# ANET3D_Board.net
KiCad netlist of a schematic drawn in EAGLE
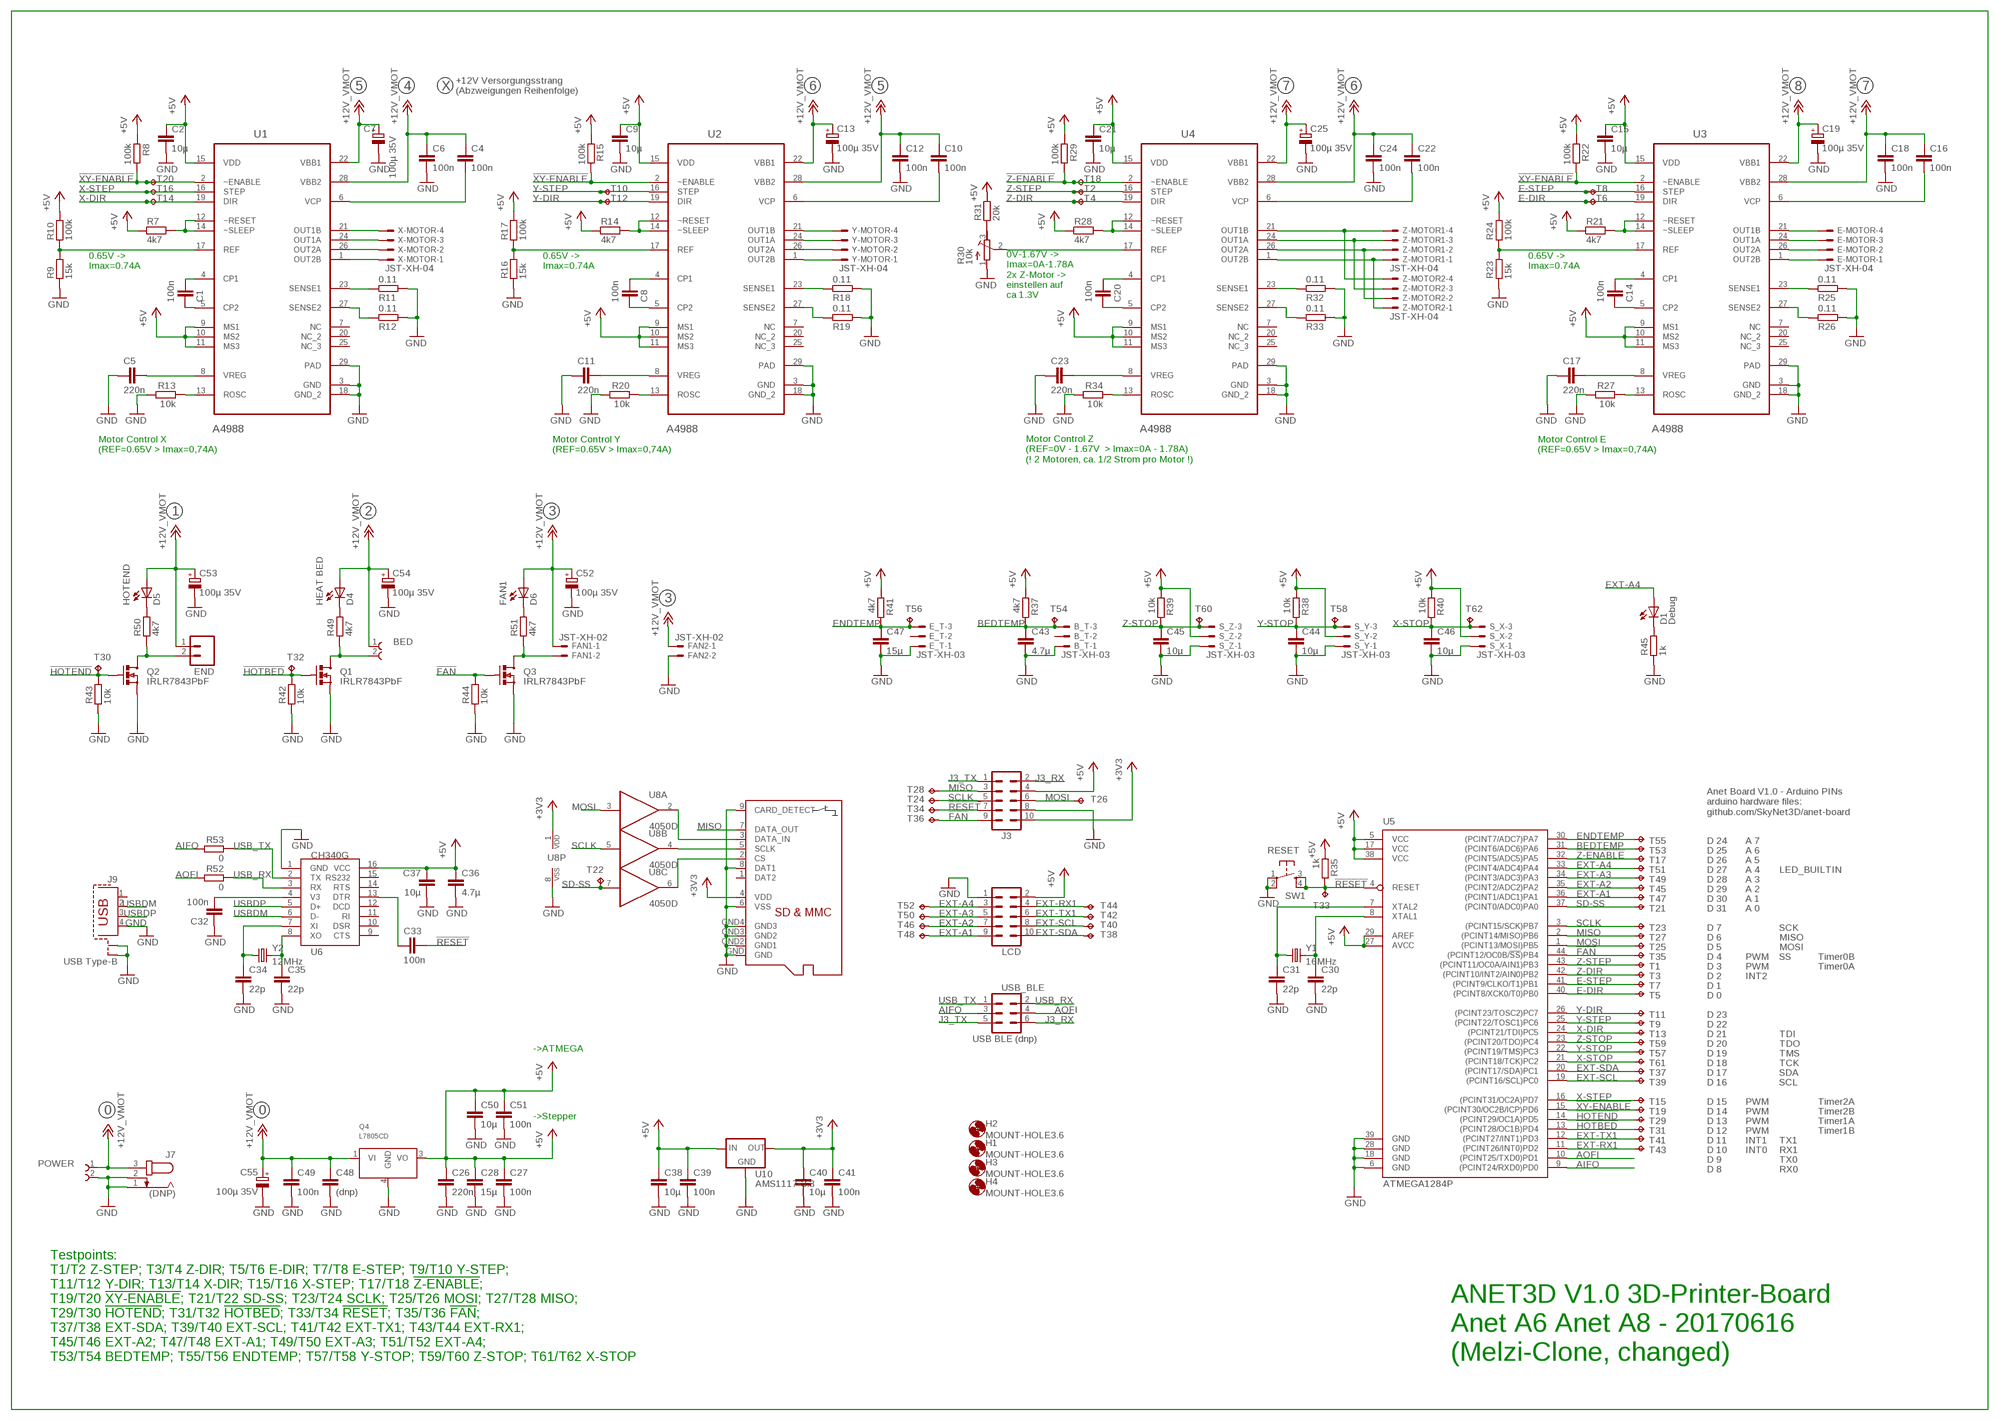
[diagram p0: schematic, sheet 1]

(export (version "E")
  (design (tool "Eeschema 10.0.6"))
  (components
    (comp (ref "BED")
      (value "691311400002")
      (footprint "eagle-import:691311400002")
      (libsource (lib "eagle-import") (part "691311400002"))
    )
    (comp (ref "B_T")
      (value "JST-XH-03")
      (footprint "eagle-import:JST-XH-03-PACKAGE-ROUND-PAD")
      (libsource (lib "eagle-import") (part "JST-XH-03-PIN-ROUND-PAD"))
    )
    (comp (ref "C1")
      (value "100n")
      (footprint "eagle-import:C0805")
      (libsource (lib "eagle-import") (part "C-EUC0805"))
    )
    (comp (ref "C2")
      (value "10µ")
      (footprint "eagle-import:C0805")
      (libsource (lib "eagle-import") (part "C-EUC0805"))
    )
    (comp (ref "C4")
      (value "100n")
      (footprint "eagle-import:C0805")
      (libsource (lib "eagle-import") (part "C-EUC0805"))
    )
    (comp (ref "C5")
      (value "220n")
      (footprint "eagle-import:C0805")
      (libsource (lib "eagle-import") (part "C-EUC0805"))
    )
    (comp (ref "C6")
      (value "100n")
      (footprint "eagle-import:C0805")
      (libsource (lib "eagle-import") (part "C-EUC0805"))
    )
    (comp (ref "C7")
      (value "100µ 35V")
      (footprint "eagle-import:PANASONIC_D")
      (libsource (lib "eagle-import") (part "CPOL-EUD"))
    )
    (comp (ref "C8")
      (value "100n")
      (footprint "eagle-import:C0805")
      (libsource (lib "eagle-import") (part "C-EUC0805"))
    )
    (comp (ref "C9")
      (value "10µ")
      (footprint "eagle-import:C0805")
      (libsource (lib "eagle-import") (part "C-EUC0805"))
    )
    (comp (ref "C10")
      (value "100n")
      (footprint "eagle-import:C0805")
      (libsource (lib "eagle-import") (part "C-EUC0805"))
    )
    (comp (ref "C11")
      (value "220n")
      (footprint "eagle-import:C0805")
      (libsource (lib "eagle-import") (part "C-EUC0805"))
    )
    (comp (ref "C12")
      (value "100n")
      (footprint "eagle-import:C0805")
      (libsource (lib "eagle-import") (part "C-EUC0805"))
    )
    (comp (ref "C13")
      (value "100µ 35V")
      (footprint "eagle-import:PANASONIC_D")
      (libsource (lib "eagle-import") (part "CPOL-EUD"))
    )
    (comp (ref "C14")
      (value "100n")
      (footprint "eagle-import:C0805")
      (libsource (lib "eagle-import") (part "C-EUC0805"))
    )
    (comp (ref "C15")
      (value "10µ")
      (footprint "eagle-import:C0805")
      (libsource (lib "eagle-import") (part "C-EUC0805"))
    )
    (comp (ref "C16")
      (value "100n")
      (footprint "eagle-import:C0805")
      (libsource (lib "eagle-import") (part "C-EUC0805"))
    )
    (comp (ref "C17")
      (value "220n")
      (footprint "eagle-import:C0805")
      (libsource (lib "eagle-import") (part "C-EUC0805"))
    )
    (comp (ref "C18")
      (value "100n")
      (footprint "eagle-import:C0805")
      (libsource (lib "eagle-import") (part "C-EUC0805"))
    )
    (comp (ref "C19")
      (value "100µ 35V")
      (footprint "eagle-import:PANASONIC_D")
      (libsource (lib "eagle-import") (part "CPOL-EUD"))
    )
    (comp (ref "C20")
      (value "100n")
      (footprint "eagle-import:C0805")
      (libsource (lib "eagle-import") (part "C-EUC0805"))
    )
    (comp (ref "C21")
      (value "10µ")
      (footprint "eagle-import:C0805")
      (libsource (lib "eagle-import") (part "C-EUC0805"))
    )
    (comp (ref "C22")
      (value "100n")
      (footprint "eagle-import:C0805")
      (libsource (lib "eagle-import") (part "C-EUC0805"))
    )
    (comp (ref "C23")
      (value "220n")
      (footprint "eagle-import:C0805")
      (libsource (lib "eagle-import") (part "C-EUC0805"))
    )
    (comp (ref "C24")
      (value "100n")
      (footprint "eagle-import:C0805")
      (libsource (lib "eagle-import") (part "C-EUC0805"))
    )
    (comp (ref "C25")
      (value "100µ 35V")
      (footprint "eagle-import:PANASONIC_D")
      (libsource (lib "eagle-import") (part "CPOL-EUD"))
    )
    (comp (ref "C26")
      (value "220n")
      (footprint "eagle-import:C0805")
      (libsource (lib "eagle-import") (part "C-EUC0805"))
    )
    (comp (ref "C27")
      (value "100n")
      (footprint "eagle-import:C0805")
      (libsource (lib "eagle-import") (part "C-EUC0805"))
    )
    (comp (ref "C28")
      (value "15µ")
      (footprint "eagle-import:C0805")
      (libsource (lib "eagle-import") (part "C-EUC0805"))
    )
    (comp (ref "C30")
      (value "22p")
      (footprint "eagle-import:C0805")
      (libsource (lib "eagle-import") (part "C-EUC0805"))
    )
    (comp (ref "C31")
      (value "22p")
      (footprint "eagle-import:C0805")
      (libsource (lib "eagle-import") (part "C-EUC0805"))
    )
    (comp (ref "C32")
      (value "100n")
      (footprint "eagle-import:C0805")
      (libsource (lib "eagle-import") (part "C-EUC0805"))
    )
    (comp (ref "C33")
      (value "100n")
      (footprint "eagle-import:C0805")
      (libsource (lib "eagle-import") (part "C-EUC0805"))
    )
    (comp (ref "C34")
      (value "22p")
      (footprint "eagle-import:C0805")
      (libsource (lib "eagle-import") (part "C-EUC0805"))
    )
    (comp (ref "C35")
      (value "22p")
      (footprint "eagle-import:C0805")
      (libsource (lib "eagle-import") (part "C-EUC0805"))
    )
    (comp (ref "C36")
      (value "4.7µ")
      (footprint "eagle-import:C0805")
      (libsource (lib "eagle-import") (part "C-EUC0805"))
    )
    (comp (ref "C37")
      (value "10µ")
      (footprint "eagle-import:C0805")
      (libsource (lib "eagle-import") (part "C-EUC0805"))
    )
    (comp (ref "C38")
      (value "10µ")
      (footprint "eagle-import:C0805")
      (libsource (lib "eagle-import") (part "C-EUC0805"))
    )
    (comp (ref "C39")
      (value "100n")
      (footprint "eagle-import:C0805")
      (libsource (lib "eagle-import") (part "C-EUC0805"))
    )
    (comp (ref "C40")
      (value "10µ")
      (footprint "eagle-import:C0805")
      (libsource (lib "eagle-import") (part "C-EUC0805"))
    )
    (comp (ref "C41")
      (value "100n")
      (footprint "eagle-import:C0805")
      (libsource (lib "eagle-import") (part "C-EUC0805"))
    )
    (comp (ref "C43")
      (value "4.7µ")
      (footprint "eagle-import:C0805")
      (libsource (lib "eagle-import") (part "C-EUC0805"))
    )
    (comp (ref "C44")
      (value "10µ")
      (footprint "eagle-import:C0805")
      (libsource (lib "eagle-import") (part "C-EUC0805"))
    )
    (comp (ref "C45")
      (value "10µ")
      (footprint "eagle-import:C0805")
      (libsource (lib "eagle-import") (part "C-EUC0805"))
    )
    (comp (ref "C46")
      (value "10µ")
      (footprint "eagle-import:C0805")
      (libsource (lib "eagle-import") (part "C-EUC0805"))
    )
    (comp (ref "C47")
      (value "15µ")
      (footprint "eagle-import:C0805")
      (libsource (lib "eagle-import") (part "C-EUC0805"))
    )
    (comp (ref "C48")
      (value "(dnp)")
      (footprint "eagle-import:C0805")
      (libsource (lib "eagle-import") (part "C-EUC0805"))
    )
    (comp (ref "C49")
      (value "100n")
      (footprint "eagle-import:C0805")
      (libsource (lib "eagle-import") (part "C-EUC0805"))
    )
    (comp (ref "C50")
      (value "10µ")
      (footprint "eagle-import:C0805")
      (libsource (lib "eagle-import") (part "C-EUC0805"))
    )
    (comp (ref "C51")
      (value "100n")
      (footprint "eagle-import:C0805")
      (libsource (lib "eagle-import") (part "C-EUC0805"))
    )
    (comp (ref "C52")
      (value "100µ 35V")
      (footprint "eagle-import:PANASONIC_D")
      (libsource (lib "eagle-import") (part "CPOL-EUD"))
    )
    (comp (ref "C53")
      (value "100µ 35V")
      (footprint "eagle-import:PANASONIC_D")
      (libsource (lib "eagle-import") (part "CPOL-EUD"))
    )
    (comp (ref "C54")
      (value "100µ 35V")
      (footprint "eagle-import:PANASONIC_D")
      (libsource (lib "eagle-import") (part "CPOL-EUD"))
    )
    (comp (ref "C55")
      (value "100µ 35V")
      (footprint "eagle-import:PANASONIC_D")
      (libsource (lib "eagle-import") (part "CPOL-EUD"))
    )
    (comp (ref "D1")
      (value "Debug")
      (footprint "eagle-import:CHIPLED_0805")
      (libsource (lib "eagle-import") (part "LEDCHIPLED_0805"))
    )
    (comp (ref "D4")
      (value "HEAT BED")
      (footprint "eagle-import:CHIPLED_0805")
      (libsource (lib "eagle-import") (part "LEDCHIPLED_0805"))
    )
    (comp (ref "D5")
      (value "HOTEND")
      (footprint "eagle-import:CHIPLED_0805")
      (libsource (lib "eagle-import") (part "LEDCHIPLED_0805"))
    )
    (comp (ref "D6")
      (value "FAN1")
      (footprint "eagle-import:CHIPLED_0805")
      (libsource (lib "eagle-import") (part "LEDCHIPLED_0805"))
    )
    (comp (ref "E-MOTOR")
      (value "JST-XH-04")
      (footprint "eagle-import:JST-XH-04-PACKAGE-ROUND-PAD")
      (libsource (lib "eagle-import") (part "JST-XH-04-PIN-ROUND-PAD"))
    )
    (comp (ref "END")
      (value "M025MM")
      (footprint "eagle-import:SCREWTERMINAL-5MM-2")
      (libsource (lib "eagle-import") (part "M025MM"))
    )
    (comp (ref "E_T")
      (value "JST-XH-03")
      (footprint "eagle-import:JST-XH-03-PACKAGE-ROUND-PAD")
      (libsource (lib "eagle-import") (part "JST-XH-03-PIN-ROUND-PAD"))
    )
    (comp (ref "FAN1")
      (value "JST-XH-02")
      (footprint "eagle-import:JST-XH-02-PACKAGE-ROUND-PAD")
      (libsource (lib "eagle-import") (part "JST-XH-02-PIN-ROUND-PAD"))
    )
    (comp (ref "FAN2")
      (value "JST-XH-02")
      (footprint "eagle-import:JST-XH-02-PACKAGE-ROUND-PAD")
      (libsource (lib "eagle-import") (part "JST-XH-02-PIN-ROUND-PAD"))
    )
    (comp (ref "H1")
      (value "MOUNT-HOLE3.6")
      (footprint "eagle-import:3,6")
      (libsource (lib "eagle-import") (part "MOUNT-HOLE3.6"))
    )
    (comp (ref "H2")
      (value "MOUNT-HOLE3.6")
      (footprint "eagle-import:3,6")
      (libsource (lib "eagle-import") (part "MOUNT-HOLE3.6"))
    )
    (comp (ref "H3")
      (value "MOUNT-HOLE3.6")
      (footprint "eagle-import:3,6")
      (libsource (lib "eagle-import") (part "MOUNT-HOLE3.6"))
    )
    (comp (ref "H4")
      (value "MOUNT-HOLE3.6")
      (footprint "eagle-import:3,6")
      (libsource (lib "eagle-import") (part "MOUNT-HOLE3.6"))
    )
    (comp (ref "J3")
      (value "J3")
      (footprint "eagle-import:ML10")
      (libsource (lib "eagle-import") (part "ML10"))
    )
    (comp (ref "J7")
      (value "(DNP)")
      (footprint "eagle-import:SPC4078")
      (libsource (lib "eagle-import") (part "JACK-PLUG1"))
    )
    (comp (ref "J9")
      (value "USB Type-B")
      (footprint "eagle-import:PN61729-S")
      (libsource (lib "eagle-import") (part "PN61729-S"))
    )
    (comp (ref "LCD")
      (value "LCD")
      (footprint "eagle-import:ML10")
      (libsource (lib "eagle-import") (part "ML10"))
    )
    (comp (ref "POWER")
      (value "691311400002")
      (footprint "eagle-import:691311400002")
      (libsource (lib "eagle-import") (part "691311400002"))
    )
    (comp (ref "Q1")
      (value "IRLR7843PbF")
      (footprint "eagle-import:DPAK")
      (libsource (lib "eagle-import") (part "MOSFET-NCHANNELFDD8580"))
    )
    (comp (ref "Q2")
      (value "IRLR7843PbF")
      (footprint "eagle-import:DPAK")
      (libsource (lib "eagle-import") (part "MOSFET-NCHANNELFDD8580"))
    )
    (comp (ref "Q3")
      (value "IRLR7843PbF")
      (footprint "eagle-import:DPAK")
      (libsource (lib "eagle-import") (part "MOSFET-NCHANNELFDD8580"))
    )
    (comp (ref "Q4")
      (value "L7805CD")
      (footprint "eagle-import:D2PACK")
      (libsource (lib "eagle-import") (part "78XX"))
    )
    (comp (ref "R7")
      (value "4k7")
      (footprint "eagle-import:RESC2012X70N")
      (libsource (lib "eagle-import") (part "RESISTOR_0805"))
    )
    (comp (ref "R8")
      (value "100k")
      (footprint "eagle-import:RESC2012X70N")
      (libsource (lib "eagle-import") (part "RESISTOR_0805"))
    )
    (comp (ref "R9")
      (value "15k")
      (footprint "eagle-import:RESC2012X70N")
      (libsource (lib "eagle-import") (part "RESISTOR_0805"))
    )
    (comp (ref "R10")
      (value "100k")
      (footprint "eagle-import:RESC2012X70N")
      (libsource (lib "eagle-import") (part "RESISTOR_0805"))
    )
    (comp (ref "R11")
      (value "0.11")
      (footprint "eagle-import:RESC2012X70N")
      (libsource (lib "eagle-import") (part "RESISTOR_0805"))
    )
    (comp (ref "R12")
      (value "0.11")
      (footprint "eagle-import:RESC2012X70N")
      (libsource (lib "eagle-import") (part "RESISTOR_0805"))
    )
    (comp (ref "R13")
      (value "10k")
      (footprint "eagle-import:RESC2012X70N")
      (libsource (lib "eagle-import") (part "RESISTOR_0805"))
    )
    (comp (ref "R14")
      (value "4k7")
      (footprint "eagle-import:RESC2012X70N")
      (libsource (lib "eagle-import") (part "RESISTOR_0805"))
    )
    (comp (ref "R15")
      (value "100k")
      (footprint "eagle-import:RESC2012X70N")
      (libsource (lib "eagle-import") (part "RESISTOR_0805"))
    )
    (comp (ref "R16")
      (value "15k")
      (footprint "eagle-import:RESC2012X70N")
      (libsource (lib "eagle-import") (part "RESISTOR_0805"))
    )
    (comp (ref "R17")
      (value "100k")
      (footprint "eagle-import:RESC2012X70N")
      (libsource (lib "eagle-import") (part "RESISTOR_0805"))
    )
    (comp (ref "R18")
      (value "0.11")
      (footprint "eagle-import:RESC2012X70N")
      (libsource (lib "eagle-import") (part "RESISTOR_0805"))
    )
    (comp (ref "R19")
      (value "0.11")
      (footprint "eagle-import:RESC2012X70N")
      (libsource (lib "eagle-import") (part "RESISTOR_0805"))
    )
    (comp (ref "R20")
      (value "10k")
      (footprint "eagle-import:RESC2012X70N")
      (libsource (lib "eagle-import") (part "RESISTOR_0805"))
    )
    (comp (ref "R21")
      (value "4k7")
      (footprint "eagle-import:RESC2012X70N")
      (libsource (lib "eagle-import") (part "RESISTOR_0805"))
    )
    (comp (ref "R22")
      (value "100k")
      (footprint "eagle-import:RESC2012X70N")
      (libsource (lib "eagle-import") (part "RESISTOR_0805"))
    )
    (comp (ref "R23")
      (value "15k")
      (footprint "eagle-import:RESC2012X70N")
      (libsource (lib "eagle-import") (part "RESISTOR_0805"))
    )
    (comp (ref "R24")
      (value "100k")
      (footprint "eagle-import:RESC2012X70N")
      (libsource (lib "eagle-import") (part "RESISTOR_0805"))
    )
    (comp (ref "R25")
      (value "0.11")
      (footprint "eagle-import:RESC2012X70N")
      (libsource (lib "eagle-import") (part "RESISTOR_0805"))
    )
    (comp (ref "R26")
      (value "0.11")
      (footprint "eagle-import:RESC2012X70N")
      (libsource (lib "eagle-import") (part "RESISTOR_0805"))
    )
    (comp (ref "R27")
      (value "10k")
      (footprint "eagle-import:RESC2012X70N")
      (libsource (lib "eagle-import") (part "RESISTOR_0805"))
    )
    (comp (ref "R28")
      (value "4k7")
      (footprint "eagle-import:RESC2012X70N")
      (libsource (lib "eagle-import") (part "RESISTOR_0805"))
    )
    (comp (ref "R29")
      (value "100k")
      (footprint "eagle-import:RESC2012X70N")
      (libsource (lib "eagle-import") (part "RESISTOR_0805"))
    )
    (comp (ref "R30")
      (value "10k")
      (footprint "eagle-import:RTRIM3374")
      (libsource (lib "eagle-import") (part "R-TRIMM3374"))
    )
    (comp (ref "R31")
      (value "20k")
      (footprint "eagle-import:RESC2012X70N")
      (libsource (lib "eagle-import") (part "RESISTOR_0805"))
    )
    (comp (ref "R32")
      (value "0.11")
      (footprint "eagle-import:RESC2012X70N")
      (libsource (lib "eagle-import") (part "RESISTOR_0805"))
    )
    (comp (ref "R33")
      (value "0.11")
      (footprint "eagle-import:RESC2012X70N")
      (libsource (lib "eagle-import") (part "RESISTOR_0805"))
    )
    (comp (ref "R34")
      (value "10k")
      (footprint "eagle-import:RESC2012X70N")
      (libsource (lib "eagle-import") (part "RESISTOR_0805"))
    )
    (comp (ref "R35")
      (value "1k")
      (footprint "eagle-import:RESC2012X70N")
      (libsource (lib "eagle-import") (part "RESISTOR_0805"))
    )
    (comp (ref "R37")
      (value "4k7")
      (footprint "eagle-import:RESC2012X70N")
      (libsource (lib "eagle-import") (part "RESISTOR_0805"))
    )
    (comp (ref "R38")
      (value "10k")
      (footprint "eagle-import:RESC2012X70N")
      (libsource (lib "eagle-import") (part "RESISTOR_0805"))
    )
    (comp (ref "R39")
      (value "10k")
      (footprint "eagle-import:RESC2012X70N")
      (libsource (lib "eagle-import") (part "RESISTOR_0805"))
    )
    (comp (ref "R40")
      (value "10k")
      (footprint "eagle-import:RESC2012X70N")
      (libsource (lib "eagle-import") (part "RESISTOR_0805"))
    )
    (comp (ref "R41")
      (value "4k7")
      (footprint "eagle-import:RESC2012X70N")
      (libsource (lib "eagle-import") (part "RESISTOR_0805"))
    )
    (comp (ref "R42")
      (value "10k")
      (footprint "eagle-import:RESC2012X70N")
      (libsource (lib "eagle-import") (part "RESISTOR_0805"))
    )
    (comp (ref "R43")
      (value "10k")
      (footprint "eagle-import:RESC2012X70N")
      (libsource (lib "eagle-import") (part "RESISTOR_0805"))
    )
    (comp (ref "R44")
      (value "10k")
      (footprint "eagle-import:RESC2012X70N")
      (libsource (lib "eagle-import") (part "RESISTOR_0805"))
    )
    (comp (ref "R45")
      (value "1k")
      (footprint "eagle-import:RESC2012X70N")
      (libsource (lib "eagle-import") (part "RESISTOR_0805"))
    )
    (comp (ref "R49")
      (value "4k7")
      (footprint "eagle-import:RESC2012X70N")
      (libsource (lib "eagle-import") (part "RESISTOR_0805"))
    )
    (comp (ref "R50")
      (value "4k7")
      (footprint "eagle-import:RESC2012X70N")
      (libsource (lib "eagle-import") (part "RESISTOR_0805"))
    )
    (comp (ref "R51")
      (value "4k7")
      (footprint "eagle-import:RESC2012X70N")
      (libsource (lib "eagle-import") (part "RESISTOR_0805"))
    )
    (comp (ref "R52")
      (value "0")
      (footprint "eagle-import:RESC2012X70N")
      (libsource (lib "eagle-import") (part "RESISTOR_0805"))
    )
    (comp (ref "R53")
      (value "0")
      (footprint "eagle-import:RESC2012X70N")
      (libsource (lib "eagle-import") (part "RESISTOR_0805"))
    )
    (comp (ref "SD")
      (value "MICRO-SD-PP")
      (footprint "eagle-import:MICRO-SD-PP")
      (libsource (lib "eagle-import") (part "MICRO-SD-PP"))
    )
    (comp (ref "SW1")
      (value "RESET")
      (footprint "eagle-import:TACTILE_SWITCH_SMD")
      (libsource (lib "eagle-import") (part "TAC_SWITCHSMD"))
    )
    (comp (ref "S_X")
      (value "JST-XH-03")
      (footprint "eagle-import:JST-XH-03-PACKAGE-ROUND-PAD")
      (libsource (lib "eagle-import") (part "JST-XH-03-PIN-ROUND-PAD"))
    )
    (comp (ref "S_Y")
      (value "JST-XH-03")
      (footprint "eagle-import:JST-XH-03-PACKAGE-ROUND-PAD")
      (libsource (lib "eagle-import") (part "JST-XH-03-PIN-ROUND-PAD"))
    )
    (comp (ref "S_Z")
      (value "JST-XH-03")
      (footprint "eagle-import:JST-XH-03-PACKAGE-ROUND-PAD")
      (libsource (lib "eagle-import") (part "JST-XH-03-PIN-ROUND-PAD"))
    )
    (comp (ref "T1")
      (value "TPTP09R")
      (footprint "eagle-import:TP09R")
      (libsource (lib "eagle-import") (part "TPTP09R"))
    )
    (comp (ref "T2")
      (value "TPTP09R")
      (footprint "eagle-import:TP09R")
      (libsource (lib "eagle-import") (part "TPTP09R"))
    )
    (comp (ref "T3")
      (value "TPTP09R")
      (footprint "eagle-import:TP09R")
      (libsource (lib "eagle-import") (part "TPTP09R"))
    )
    (comp (ref "T4")
      (value "TPTP09R")
      (footprint "eagle-import:TP09R")
      (libsource (lib "eagle-import") (part "TPTP09R"))
    )
    (comp (ref "T5")
      (value "TPTP09R")
      (footprint "eagle-import:TP09R")
      (libsource (lib "eagle-import") (part "TPTP09R"))
    )
    (comp (ref "T6")
      (value "TPTP09R")
      (footprint "eagle-import:TP09R")
      (libsource (lib "eagle-import") (part "TPTP09R"))
    )
    (comp (ref "T7")
      (value "TPTP09R")
      (footprint "eagle-import:TP09R")
      (libsource (lib "eagle-import") (part "TPTP09R"))
    )
    (comp (ref "T8")
      (value "TPTP09R")
      (footprint "eagle-import:TP09R")
      (libsource (lib "eagle-import") (part "TPTP09R"))
    )
    (comp (ref "T9")
      (value "TPTP09R")
      (footprint "eagle-import:TP09R")
      (libsource (lib "eagle-import") (part "TPTP09R"))
    )
    (comp (ref "T10")
      (value "TPTP09R")
      (footprint "eagle-import:TP09R")
      (libsource (lib "eagle-import") (part "TPTP09R"))
    )
    (comp (ref "T11")
      (value "TPTP09R")
      (footprint "eagle-import:TP09R")
      (libsource (lib "eagle-import") (part "TPTP09R"))
    )
    (comp (ref "T12")
      (value "TPTP09R")
      (footprint "eagle-import:TP09R")
      (libsource (lib "eagle-import") (part "TPTP09R"))
    )
    (comp (ref "T13")
      (value "TPTP09R")
      (footprint "eagle-import:TP09R")
      (libsource (lib "eagle-import") (part "TPTP09R"))
    )
    (comp (ref "T14")
      (value "TPTP09R")
      (footprint "eagle-import:TP09R")
      (libsource (lib "eagle-import") (part "TPTP09R"))
    )
    (comp (ref "T15")
      (value "TPTP09R")
      (footprint "eagle-import:TP09R")
      (libsource (lib "eagle-import") (part "TPTP09R"))
    )
    (comp (ref "T16")
      (value "TPTP09R")
      (footprint "eagle-import:TP09R")
      (libsource (lib "eagle-import") (part "TPTP09R"))
    )
    (comp (ref "T17")
      (value "TPTP09R")
      (footprint "eagle-import:TP09R")
      (libsource (lib "eagle-import") (part "TPTP09R"))
    )
    (comp (ref "T18")
      (value "TPTP09R")
      (footprint "eagle-import:TP09R")
      (libsource (lib "eagle-import") (part "TPTP09R"))
    )
    (comp (ref "T19")
      (value "TPTP09R")
      (footprint "eagle-import:TP09R")
      (libsource (lib "eagle-import") (part "TPTP09R"))
    )
    (comp (ref "T20")
      (value "TPTP09R")
      (footprint "eagle-import:TP09R")
      (libsource (lib "eagle-import") (part "TPTP09R"))
    )
    (comp (ref "T21")
      (value "TPTP09R")
      (footprint "eagle-import:TP09R")
      (libsource (lib "eagle-import") (part "TPTP09R"))
    )
    (comp (ref "T22")
      (value "TPTP09R")
      (footprint "eagle-import:TP09R")
      (libsource (lib "eagle-import") (part "TPTP09R"))
    )
    (comp (ref "T23")
      (value "TPTP09R")
      (footprint "eagle-import:TP09R")
      (libsource (lib "eagle-import") (part "TPTP09R"))
    )
    (comp (ref "T24")
      (value "TPTP09R")
      (footprint "eagle-import:TP09R")
      (libsource (lib "eagle-import") (part "TPTP09R"))
    )
    (comp (ref "T25")
      (value "TPTP09R")
      (footprint "eagle-import:TP09R")
      (libsource (lib "eagle-import") (part "TPTP09R"))
    )
    (comp (ref "T26")
      (value "TPTP09R")
      (footprint "eagle-import:TP09R")
      (libsource (lib "eagle-import") (part "TPTP09R"))
    )
    (comp (ref "T27")
      (value "TPTP09R")
      (footprint "eagle-import:TP09R")
      (libsource (lib "eagle-import") (part "TPTP09R"))
    )
    (comp (ref "T28")
      (value "TPTP09R")
      (footprint "eagle-import:TP09R")
      (libsource (lib "eagle-import") (part "TPTP09R"))
    )
    (comp (ref "T29")
      (value "TPTP09R")
      (footprint "eagle-import:TP09R")
      (libsource (lib "eagle-import") (part "TPTP09R"))
    )
    (comp (ref "T30")
      (value "TPTP09R")
      (footprint "eagle-import:TP09R")
      (libsource (lib "eagle-import") (part "TPTP09R"))
    )
    (comp (ref "T31")
      (value "TPTP09R")
      (footprint "eagle-import:TP09R")
      (libsource (lib "eagle-import") (part "TPTP09R"))
    )
    (comp (ref "T32")
      (value "TPTP09R")
      (footprint "eagle-import:TP09R")
      (libsource (lib "eagle-import") (part "TPTP09R"))
    )
    (comp (ref "T33")
      (value "TPTP09R")
      (footprint "eagle-import:TP09R")
      (libsource (lib "eagle-import") (part "TPTP09R"))
    )
    (comp (ref "T34")
      (value "TPTP09R")
      (footprint "eagle-import:TP09R")
      (libsource (lib "eagle-import") (part "TPTP09R"))
    )
    (comp (ref "T35")
      (value "TPTP09R")
      (footprint "eagle-import:TP09R")
      (libsource (lib "eagle-import") (part "TPTP09R"))
    )
    (comp (ref "T36")
      (value "TPTP09R")
      (footprint "eagle-import:TP09R")
      (libsource (lib "eagle-import") (part "TPTP09R"))
    )
    (comp (ref "T37")
      (value "TPTP09R")
      (footprint "eagle-import:TP09R")
      (libsource (lib "eagle-import") (part "TPTP09R"))
    )
    (comp (ref "T38")
      (value "TPTP09R")
      (footprint "eagle-import:TP09R")
      (libsource (lib "eagle-import") (part "TPTP09R"))
    )
    (comp (ref "T39")
      (value "TPTP09R")
      (footprint "eagle-import:TP09R")
      (libsource (lib "eagle-import") (part "TPTP09R"))
    )
    (comp (ref "T40")
      (value "TPTP09R")
      (footprint "eagle-import:TP09R")
      (libsource (lib "eagle-import") (part "TPTP09R"))
    )
    (comp (ref "T41")
      (value "TPTP09R")
      (footprint "eagle-import:TP09R")
      (libsource (lib "eagle-import") (part "TPTP09R"))
    )
    (comp (ref "T42")
      (value "TPTP09R")
      (footprint "eagle-import:TP09R")
      (libsource (lib "eagle-import") (part "TPTP09R"))
    )
    (comp (ref "T43")
      (value "TPTP09R")
      (footprint "eagle-import:TP09R")
      (libsource (lib "eagle-import") (part "TPTP09R"))
    )
    (comp (ref "T44")
      (value "TPTP09R")
      (footprint "eagle-import:TP09R")
      (libsource (lib "eagle-import") (part "TPTP09R"))
    )
    (comp (ref "T45")
      (value "TPTP09R")
      (footprint "eagle-import:TP09R")
      (libsource (lib "eagle-import") (part "TPTP09R"))
    )
    (comp (ref "T46")
      (value "TPTP09R")
      (footprint "eagle-import:TP09R")
      (libsource (lib "eagle-import") (part "TPTP09R"))
    )
    (comp (ref "T47")
      (value "TPTP09R")
      (footprint "eagle-import:TP09R")
      (libsource (lib "eagle-import") (part "TPTP09R"))
    )
    (comp (ref "T48")
      (value "TPTP09R")
      (footprint "eagle-import:TP09R")
      (libsource (lib "eagle-import") (part "TPTP09R"))
    )
    (comp (ref "T49")
      (value "TPTP09R")
      (footprint "eagle-import:TP09R")
      (libsource (lib "eagle-import") (part "TPTP09R"))
    )
    (comp (ref "T50")
      (value "TPTP09R")
      (footprint "eagle-import:TP09R")
      (libsource (lib "eagle-import") (part "TPTP09R"))
    )
    (comp (ref "T51")
      (value "TPTP09R")
      (footprint "eagle-import:TP09R")
      (libsource (lib "eagle-import") (part "TPTP09R"))
    )
    (comp (ref "T52")
      (value "TPTP09R")
      (footprint "eagle-import:TP09R")
      (libsource (lib "eagle-import") (part "TPTP09R"))
    )
    (comp (ref "T53")
      (value "TPTP09R")
      (footprint "eagle-import:TP09R")
      (libsource (lib "eagle-import") (part "TPTP09R"))
    )
    (comp (ref "T54")
      (value "TPTP09R")
      (footprint "eagle-import:TP09R")
      (libsource (lib "eagle-import") (part "TPTP09R"))
    )
    (comp (ref "T55")
      (value "TPTP09R")
      (footprint "eagle-import:TP09R")
      (libsource (lib "eagle-import") (part "TPTP09R"))
    )
    (comp (ref "T56")
      (value "TPTP09R")
      (footprint "eagle-import:TP09R")
      (libsource (lib "eagle-import") (part "TPTP09R"))
    )
    (comp (ref "T57")
      (value "TPTP09R")
      (footprint "eagle-import:TP09R")
      (libsource (lib "eagle-import") (part "TPTP09R"))
    )
    (comp (ref "T58")
      (value "TPTP09R")
      (footprint "eagle-import:TP09R")
      (libsource (lib "eagle-import") (part "TPTP09R"))
    )
    (comp (ref "T59")
      (value "TPTP09R")
      (footprint "eagle-import:TP09R")
      (libsource (lib "eagle-import") (part "TPTP09R"))
    )
    (comp (ref "T60")
      (value "TPTP09R")
      (footprint "eagle-import:TP09R")
      (libsource (lib "eagle-import") (part "TPTP09R"))
    )
    (comp (ref "T61")
      (value "TPTP09R")
      (footprint "eagle-import:TP09R")
      (libsource (lib "eagle-import") (part "TPTP09R"))
    )
    (comp (ref "T62")
      (value "TPTP09R")
      (footprint "eagle-import:TP09R")
      (libsource (lib "eagle-import") (part "TPTP09R"))
    )
    (comp (ref "U1")
      (value "A4988")
      (footprint "eagle-import:QFN50P500X500X100-29N")
      (fields (field (name "MPN") "A4988SETTR-T"))
      (libsource (lib "eagle-import") (part "A4988SETTR-T-RE"))
    )
    (comp (ref "U2")
      (value "A4988")
      (footprint "eagle-import:QFN50P500X500X100-29N")
      (fields (field (name "MPN") "A4988SETTR-T"))
      (libsource (lib "eagle-import") (part "A4988SETTR-T-RE"))
    )
    (comp (ref "U3")
      (value "A4988")
      (footprint "eagle-import:QFN50P500X500X100-29N")
      (fields (field (name "MPN") "A4988SETTR-T"))
      (libsource (lib "eagle-import") (part "A4988SETTR-T-RE"))
    )
    (comp (ref "U4")
      (value "A4988")
      (footprint "eagle-import:QFN50P500X500X100-29N")
      (fields (field (name "MPN") "A4988SETTR-T"))
      (libsource (lib "eagle-import") (part "A4988SETTR-T-RE"))
    )
    (comp (ref "U5")
      (value "ATMEGA1284P")
      (footprint "eagle-import:TQFP44")
      (fields (field (name "MPN") "ATMEGA644PV-10AU"))
      (libsource (lib "eagle-import") (part "ATMEGA644A"))
    )
    (comp (ref "U6")
      (value "CH340G")
      (footprint "eagle-import:SOIC16")
      (libsource (lib "eagle-import") (part "CH340G"))
    )
    (comp (ref "U8")
      (value "4050D")
      (footprint "eagle-import:SO16")
      (libsource (lib "eagle-import") (part "4050D"))
    )
    (comp (ref "U10")
      (value "AMS1117-3.3")
      (footprint "eagle-import:SOT89")
      (libsource (lib "eagle-import") (part "LM1117DTX-SOT89"))
    )
    (comp (ref "USB_BLE")
      (value "USB BLE (dnp)")
      (footprint "eagle-import:MA03-2")
      (libsource (lib "eagle-import") (part "MA03-2"))
    )
    (comp (ref "X-MOTOR")
      (value "JST-XH-04")
      (footprint "eagle-import:JST-XH-04-PACKAGE-ROUND-PAD")
      (libsource (lib "eagle-import") (part "JST-XH-04-PIN-ROUND-PAD"))
    )
    (comp (ref "Y-MOTOR")
      (value "JST-XH-04")
      (footprint "eagle-import:JST-XH-04-PACKAGE-ROUND-PAD")
      (libsource (lib "eagle-import") (part "JST-XH-04-PIN-ROUND-PAD"))
    )
    (comp (ref "Y1")
      (value "16MHz")
      (footprint "eagle-import:SM49")
      (libsource (lib "eagle-import") (part "CRYSTALSM49"))
    )
    (comp (ref "Y2")
      (value "12MHz")
      (footprint "eagle-import:SM49")
      (libsource (lib "eagle-import") (part "CRYSTALSM49"))
    )
    (comp (ref "Z-MOTOR1")
      (value "JST-XH-04")
      (footprint "eagle-import:JST-XH-04-PACKAGE-ROUND-PAD")
      (libsource (lib "eagle-import") (part "JST-XH-04-PIN-ROUND-PAD"))
    )
    (comp (ref "Z-MOTOR2")
      (value "JST-XH-04")
      (footprint "eagle-import:JST-XH-04-PACKAGE-ROUND-PAD")
      (libsource (lib "eagle-import") (part "JST-XH-04-PIN-ROUND-PAD"))
    )
  )
  (nets
    (net (code "1") (name "+3V3") (class "Default")
      (node (ref "C40") (pin "1") (pinfunction "1_1") (pintype "passive"))
      (node (ref "C41") (pin "1") (pinfunction "1_1") (pintype "passive"))
      (node (ref "J3") (pin "10") (pinfunction "10_10") (pintype "passive"))
      (node (ref "SD") (pin "4") (pinfunction "VDD_4") (pintype "power_in"))
      (node (ref "U10") (pin "2") (pinfunction "OUT_2") (pintype "passive"))
      (node (ref "U8") (pin "1") (pinfunction "VDD_1") (pintype "power_in"))
    )
    (net (code "2") (name "+5V") (class "Default")
      (node (ref "C15") (pin "1") (pinfunction "1_1") (pintype "passive"))
      (node (ref "C2") (pin "1") (pinfunction "1_1") (pintype "passive"))
      (node (ref "C21") (pin "1") (pinfunction "1_1") (pintype "passive"))
      (node (ref "C26") (pin "1") (pinfunction "1_1") (pintype "passive"))
      (node (ref "C27") (pin "1") (pinfunction "1_1") (pintype "passive"))
      (node (ref "C28") (pin "1") (pinfunction "1_1") (pintype "passive"))
      (node (ref "C36") (pin "1") (pinfunction "1_1") (pintype "passive"))
      (node (ref "C37") (pin "1") (pinfunction "1_1") (pintype "passive"))
      (node (ref "C38") (pin "1") (pinfunction "1_1") (pintype "passive"))
      (node (ref "C39") (pin "1") (pinfunction "1_1") (pintype "passive"))
      (node (ref "C50") (pin "1") (pinfunction "1_1") (pintype "passive"))
      (node (ref "C51") (pin "1") (pinfunction "1_1") (pintype "passive"))
      (node (ref "C9") (pin "1") (pinfunction "1_1") (pintype "passive"))
      (node (ref "J3") (pin "4") (pinfunction "4_4") (pintype "passive"))
      (node (ref "LCD") (pin "2") (pinfunction "2_2") (pintype "passive"))
      (node (ref "Q4") (pin "3") (pinfunction "VO_3") (pintype "bidirectional"))
      (node (ref "R10") (pin "2") (pinfunction "2_2") (pintype "passive"))
      (node (ref "R14") (pin "1") (pinfunction "1_1") (pintype "passive"))
      (node (ref "R15") (pin "1") (pinfunction "1_1") (pintype "passive"))
      (node (ref "R17") (pin "2") (pinfunction "2_2") (pintype "passive"))
      (node (ref "R21") (pin "1") (pinfunction "1_1") (pintype "passive"))
      (node (ref "R22") (pin "1") (pinfunction "1_1") (pintype "passive"))
      (node (ref "R24") (pin "2") (pinfunction "2_2") (pintype "passive"))
      (node (ref "R28") (pin "1") (pinfunction "1_1") (pintype "passive"))
      (node (ref "R29") (pin "1") (pinfunction "1_1") (pintype "passive"))
      (node (ref "R31") (pin "2") (pinfunction "2_2") (pintype "passive"))
      (node (ref "R35") (pin "1") (pinfunction "1_1") (pintype "passive"))
      (node (ref "R37") (pin "1") (pinfunction "1_1") (pintype "passive"))
      (node (ref "R38") (pin "1") (pinfunction "1_1") (pintype "passive"))
      (node (ref "R39") (pin "1") (pinfunction "1_1") (pintype "passive"))
      (node (ref "R40") (pin "1") (pinfunction "1_1") (pintype "passive"))
      (node (ref "R41") (pin "1") (pinfunction "1_1") (pintype "passive"))
      (node (ref "R7") (pin "1") (pinfunction "1_1") (pintype "passive"))
      (node (ref "R8") (pin "1") (pinfunction "1_1") (pintype "passive"))
      (node (ref "S_X") (pin "2") (pinfunction "S_2") (pintype "passive"))
      (node (ref "S_Y") (pin "2") (pinfunction "S_2") (pintype "passive"))
      (node (ref "S_Z") (pin "2") (pinfunction "S_2") (pintype "passive"))
      (node (ref "U1") (pin "10") (pinfunction "MS2_10") (pintype "input"))
      (node (ref "U1") (pin "11") (pinfunction "MS3_11") (pintype "input"))
      (node (ref "U1") (pin "15") (pinfunction "VDD_15") (pintype "power_in"))
      (node (ref "U1") (pin "9") (pinfunction "MS1_9") (pintype "input"))
      (node (ref "U10") (pin "3") (pinfunction "IN_3") (pintype "input"))
      (node (ref "U2") (pin "10") (pinfunction "MS2_10") (pintype "input"))
      (node (ref "U2") (pin "11") (pinfunction "MS3_11") (pintype "input"))
      (node (ref "U2") (pin "15") (pinfunction "VDD_15") (pintype "power_in"))
      (node (ref "U2") (pin "9") (pinfunction "MS1_9") (pintype "input"))
      (node (ref "U3") (pin "10") (pinfunction "MS2_10") (pintype "input"))
      (node (ref "U3") (pin "11") (pinfunction "MS3_11") (pintype "input"))
      (node (ref "U3") (pin "15") (pinfunction "VDD_15") (pintype "power_in"))
      (node (ref "U3") (pin "9") (pinfunction "MS1_9") (pintype "input"))
      (node (ref "U4") (pin "10") (pinfunction "MS2_10") (pintype "input"))
      (node (ref "U4") (pin "11") (pinfunction "MS3_11") (pintype "input"))
      (node (ref "U4") (pin "15") (pinfunction "VDD_15") (pintype "power_in"))
      (node (ref "U4") (pin "9") (pinfunction "MS1_9") (pintype "input"))
      (node (ref "U5") (pin "17") (pinfunction "VCC_17") (pintype "power_in"))
      (node (ref "U5") (pin "27") (pinfunction "AVCC_27") (pintype "power_in"))
      (node (ref "U5") (pin "29") (pinfunction "AREF_29") (pintype "passive"))
      (node (ref "U5") (pin "38") (pinfunction "VCC_38") (pintype "power_in"))
      (node (ref "U5") (pin "5") (pinfunction "VCC_5") (pintype "power_in"))
      (node (ref "U6") (pin "16") (pinfunction "VCC_16") (pintype "bidirectional"))
    )
    (net (code "3") (name "+12V_VMOT") (class "Default")
      (node (ref "BED") (pin "1") (pinfunction "1_1") (pintype "passive"))
      (node (ref "C10") (pin "1") (pinfunction "1_1") (pintype "passive"))
      (node (ref "C12") (pin "1") (pinfunction "1_1") (pintype "passive"))
      (node (ref "C13") (pin "+") (pinfunction "+_+") (pintype "passive"))
      (node (ref "C16") (pin "1") (pinfunction "1_1") (pintype "passive"))
      (node (ref "C18") (pin "1") (pinfunction "1_1") (pintype "passive"))
      (node (ref "C19") (pin "+") (pinfunction "+_+") (pintype "passive"))
      (node (ref "C22") (pin "1") (pinfunction "1_1") (pintype "passive"))
      (node (ref "C24") (pin "1") (pinfunction "1_1") (pintype "passive"))
      (node (ref "C25") (pin "+") (pinfunction "+_+") (pintype "passive"))
      (node (ref "C4") (pin "1") (pinfunction "1_1") (pintype "passive"))
      (node (ref "C48") (pin "1") (pinfunction "1_1") (pintype "passive"))
      (node (ref "C49") (pin "1") (pinfunction "1_1") (pintype "passive"))
      (node (ref "C52") (pin "+") (pinfunction "+_+") (pintype "passive"))
      (node (ref "C53") (pin "+") (pinfunction "+_+") (pintype "passive"))
      (node (ref "C54") (pin "+") (pinfunction "+_+") (pintype "passive"))
      (node (ref "C55") (pin "+") (pinfunction "+_+") (pintype "passive"))
      (node (ref "C6") (pin "1") (pinfunction "1_1") (pintype "passive"))
      (node (ref "C7") (pin "+") (pinfunction "+_+") (pintype "passive"))
      (node (ref "D4") (pin "A") (pinfunction "A_A") (pintype "passive"))
      (node (ref "D5") (pin "A") (pinfunction "A_A") (pintype "passive"))
      (node (ref "D6") (pin "A") (pinfunction "A_A") (pintype "passive"))
      (node (ref "END") (pin "1") (pinfunction "1_1") (pintype "passive"))
      (node (ref "FAN1") (pin "1") (pinfunction "S_1") (pintype "passive"))
      (node (ref "FAN2") (pin "1") (pinfunction "S_1") (pintype "passive"))
      (node (ref "J7") (pin "3") (pinfunction "3_3") (pintype "passive"))
      (node (ref "POWER") (pin "1") (pinfunction "1_1") (pintype "passive"))
      (node (ref "Q4") (pin "1") (pinfunction "VI_1") (pintype "bidirectional"))
      (node (ref "U1") (pin "22") (pinfunction "VBB1_22") (pintype "power_in"))
      (node (ref "U1") (pin "28") (pinfunction "VBB2_28") (pintype "power_in"))
      (node (ref "U2") (pin "22") (pinfunction "VBB1_22") (pintype "power_in"))
      (node (ref "U2") (pin "28") (pinfunction "VBB2_28") (pintype "power_in"))
      (node (ref "U3") (pin "22") (pinfunction "VBB1_22") (pintype "power_in"))
      (node (ref "U3") (pin "28") (pinfunction "VBB2_28") (pintype "power_in"))
      (node (ref "U4") (pin "22") (pinfunction "VBB1_22") (pintype "power_in"))
      (node (ref "U4") (pin "28") (pinfunction "VBB2_28") (pintype "power_in"))
    )
    (net (code "4") (name "/AIFO") (class "Default")
      (node (ref "R53") (pin "2") (pinfunction "2_2") (pintype "passive"))
      (node (ref "U5") (pin "9") (pinfunction "(PCINT24/RXD0)PD0_9") (pintype "bidirectional"))
      (node (ref "USB_BLE") (pin "3") (pinfunction "3_3") (pintype "passive"))
    )
    (net (code "5") (name "/AOFI") (class "Default")
      (node (ref "R52") (pin "2") (pinfunction "2_2") (pintype "passive"))
      (node (ref "U5") (pin "10") (pinfunction "(PCINT25/TXD0)PD1_10") (pintype "bidirectional"))
      (node (ref "USB_BLE") (pin "4") (pinfunction "4_4") (pintype "passive"))
    )
    (net (code "6") (name "/BEDTEMP") (class "Default")
      (node (ref "B_T") (pin "3") (pinfunction "S_3") (pintype "passive"))
      (node (ref "C43") (pin "1") (pinfunction "1_1") (pintype "passive"))
      (node (ref "R37") (pin "2") (pinfunction "2_2") (pintype "passive"))
      (node (ref "T53") (pin "TP") (pinfunction "TP_TP") (pintype "input"))
      (node (ref "T54") (pin "TP") (pinfunction "TP_TP") (pintype "input"))
      (node (ref "U5") (pin "31") (pinfunction "(PCINT6/ADC6)PA6_31") (pintype "bidirectional"))
    )
    (net (code "7") (name "/E-DIR") (class "Default")
      (node (ref "T5") (pin "TP") (pinfunction "TP_TP") (pintype "input"))
      (node (ref "T6") (pin "TP") (pinfunction "TP_TP") (pintype "input"))
      (node (ref "U3") (pin "19") (pinfunction "DIR_19") (pintype "input"))
      (node (ref "U5") (pin "40") (pinfunction "(PCINT8/XCK0/T0)PB0_40") (pintype "bidirectional"))
    )
    (net (code "8") (name "/E-STEP") (class "Default")
      (node (ref "T7") (pin "TP") (pinfunction "TP_TP") (pintype "input"))
      (node (ref "T8") (pin "TP") (pinfunction "TP_TP") (pintype "input"))
      (node (ref "U3") (pin "16") (pinfunction "STEP_16") (pintype "input"))
      (node (ref "U5") (pin "41") (pinfunction "(PCINT9/CLKO/T1)PB1_41") (pintype "bidirectional"))
    )
    (net (code "9") (name "/ENDTEMP") (class "Default")
      (node (ref "C47") (pin "1") (pinfunction "1_1") (pintype "passive"))
      (node (ref "E_T") (pin "3") (pinfunction "S_3") (pintype "passive"))
      (node (ref "R41") (pin "2") (pinfunction "2_2") (pintype "passive"))
      (node (ref "T55") (pin "TP") (pinfunction "TP_TP") (pintype "input"))
      (node (ref "T56") (pin "TP") (pinfunction "TP_TP") (pintype "input"))
      (node (ref "U5") (pin "30") (pinfunction "(PCINT7/ADC7)PA7_30") (pintype "bidirectional"))
    )
    (net (code "10") (name "/EXT-A1") (class "Default")
      (node (ref "LCD") (pin "9") (pinfunction "9_9") (pintype "passive"))
      (node (ref "T47") (pin "TP") (pinfunction "TP_TP") (pintype "input"))
      (node (ref "T48") (pin "TP") (pinfunction "TP_TP") (pintype "input"))
      (node (ref "U5") (pin "36") (pinfunction "(PCINT1/ADC1)PA1_36") (pintype "bidirectional"))
    )
    (net (code "11") (name "/EXT-A2") (class "Default")
      (node (ref "LCD") (pin "7") (pinfunction "7_7") (pintype "passive"))
      (node (ref "T45") (pin "TP") (pinfunction "TP_TP") (pintype "input"))
      (node (ref "T46") (pin "TP") (pinfunction "TP_TP") (pintype "input"))
      (node (ref "U5") (pin "35") (pinfunction "(PCINT2/ADC2)PA2_35") (pintype "bidirectional"))
    )
    (net (code "12") (name "/EXT-A3") (class "Default")
      (node (ref "LCD") (pin "5") (pinfunction "5_5") (pintype "passive"))
      (node (ref "T49") (pin "TP") (pinfunction "TP_TP") (pintype "input"))
      (node (ref "T50") (pin "TP") (pinfunction "TP_TP") (pintype "input"))
      (node (ref "U5") (pin "34") (pinfunction "(PCINT3/ADC3)PA3_34") (pintype "bidirectional"))
    )
    (net (code "13") (name "/EXT-A4") (class "Default")
      (node (ref "D1") (pin "A") (pinfunction "A_A") (pintype "passive"))
      (node (ref "LCD") (pin "3") (pinfunction "3_3") (pintype "passive"))
      (node (ref "T51") (pin "TP") (pinfunction "TP_TP") (pintype "input"))
      (node (ref "T52") (pin "TP") (pinfunction "TP_TP") (pintype "input"))
      (node (ref "U5") (pin "33") (pinfunction "(PCINT4/ADC4)PA4_33") (pintype "bidirectional"))
    )
    (net (code "14") (name "/EXT-RX1") (class "Default")
      (node (ref "LCD") (pin "4") (pinfunction "4_4") (pintype "passive"))
      (node (ref "T43") (pin "TP") (pinfunction "TP_TP") (pintype "input"))
      (node (ref "T44") (pin "TP") (pinfunction "TP_TP") (pintype "input"))
      (node (ref "U5") (pin "11") (pinfunction "(PCINT26/INT0)PD2_11") (pintype "bidirectional"))
    )
    (net (code "15") (name "/EXT-SCL") (class "Default")
      (node (ref "LCD") (pin "8") (pinfunction "8_8") (pintype "passive"))
      (node (ref "T39") (pin "TP") (pinfunction "TP_TP") (pintype "input"))
      (node (ref "T40") (pin "TP") (pinfunction "TP_TP") (pintype "input"))
      (node (ref "U5") (pin "19") (pinfunction "(PCINT16/SCL)PC0_19") (pintype "output"))
    )
    (net (code "16") (name "/EXT-SDA") (class "Default")
      (node (ref "LCD") (pin "10") (pinfunction "10_10") (pintype "passive"))
      (node (ref "T37") (pin "TP") (pinfunction "TP_TP") (pintype "input"))
      (node (ref "T38") (pin "TP") (pinfunction "TP_TP") (pintype "input"))
      (node (ref "U5") (pin "20") (pinfunction "(PCINT17/SDA)PC1_20") (pintype "output"))
    )
    (net (code "17") (name "/EXT-TX1") (class "Default")
      (node (ref "LCD") (pin "6") (pinfunction "6_6") (pintype "passive"))
      (node (ref "T41") (pin "TP") (pinfunction "TP_TP") (pintype "input"))
      (node (ref "T42") (pin "TP") (pinfunction "TP_TP") (pintype "input"))
      (node (ref "U5") (pin "12") (pinfunction "(PCINT27/INT1)PD3_12") (pintype "bidirectional"))
    )
    (net (code "18") (name "/J3_RX") (class "Default")
      (node (ref "J3") (pin "2") (pinfunction "2_2") (pintype "passive"))
      (node (ref "USB_BLE") (pin "6") (pinfunction "6_6") (pintype "passive"))
    )
    (net (code "19") (name "/J3_TX") (class "Default")
      (node (ref "J3") (pin "1") (pinfunction "1_1") (pintype "passive"))
      (node (ref "USB_BLE") (pin "5") (pinfunction "5_5") (pintype "passive"))
    )
    (net (code "20") (name "/MISO") (class "Default")
      (node (ref "J3") (pin "3") (pinfunction "3_3") (pintype "passive"))
      (node (ref "SD") (pin "7") (pinfunction "DATA_OUT_7") (pintype "output"))
      (node (ref "T27") (pin "TP") (pinfunction "TP_TP") (pintype "input"))
      (node (ref "T28") (pin "TP") (pinfunction "TP_TP") (pintype "input"))
      (node (ref "U5") (pin "2") (pinfunction "(PCINT14/MISO)PB6_2") (pintype "bidirectional"))
    )
    (net (code "21") (name "/MOSI") (class "Default")
      (node (ref "J3") (pin "6") (pinfunction "6_6") (pintype "passive"))
      (node (ref "T25") (pin "TP") (pinfunction "TP_TP") (pintype "input"))
      (node (ref "T26") (pin "TP") (pinfunction "TP_TP") (pintype "input"))
      (node (ref "U5") (pin "1") (pinfunction "(PCINT13/MOSI)PB5_1") (pintype "bidirectional"))
      (node (ref "U8") (pin "3") (pinfunction "I_3") (pintype "input"))
    )
    (net (code "22") (name "/SCLK") (class "Default")
      (node (ref "J3") (pin "5") (pinfunction "5_5") (pintype "passive"))
      (node (ref "T23") (pin "TP") (pinfunction "TP_TP") (pintype "input"))
      (node (ref "T24") (pin "TP") (pinfunction "TP_TP") (pintype "input"))
      (node (ref "U5") (pin "3") (pinfunction "(PCINT15/SCK)PB7_3") (pintype "bidirectional"))
      (node (ref "U8") (pin "5") (pinfunction "I_5") (pintype "input"))
    )
    (net (code "23") (name "/SD-SS") (class "Default")
      (node (ref "T21") (pin "TP") (pinfunction "TP_TP") (pintype "input"))
      (node (ref "T22") (pin "TP") (pinfunction "TP_TP") (pintype "input"))
      (node (ref "U5") (pin "37") (pinfunction "(PCINT0/ADC0)PA0_37") (pintype "bidirectional"))
      (node (ref "U8") (pin "7") (pinfunction "I_7") (pintype "input"))
    )
    (net (code "24") (name "/USBDM") (class "Default")
      (node (ref "J9") (pin "2") (pinfunction "2_2") (pintype "passive"))
      (node (ref "U6") (pin "6") (pinfunction "D-_6") (pintype "bidirectional"))
    )
    (net (code "25") (name "/USBDP") (class "Default")
      (node (ref "J9") (pin "3") (pinfunction "3_3") (pintype "passive"))
      (node (ref "U6") (pin "5") (pinfunction "D+_5") (pintype "bidirectional"))
    )
    (net (code "26") (name "/USB_RX") (class "Default")
      (node (ref "R52") (pin "1") (pinfunction "1_1") (pintype "passive"))
      (node (ref "U6") (pin "3") (pinfunction "RX_3") (pintype "bidirectional"))
      (node (ref "USB_BLE") (pin "2") (pinfunction "2_2") (pintype "passive"))
    )
    (net (code "27") (name "/USB_TX") (class "Default")
      (node (ref "R53") (pin "1") (pinfunction "1_1") (pintype "passive"))
      (node (ref "U6") (pin "2") (pinfunction "TX_2") (pintype "bidirectional"))
      (node (ref "USB_BLE") (pin "1") (pinfunction "1_1") (pintype "passive"))
    )
    (net (code "28") (name "/X-DIR") (class "Default")
      (node (ref "T13") (pin "TP") (pinfunction "TP_TP") (pintype "input"))
      (node (ref "T14") (pin "TP") (pinfunction "TP_TP") (pintype "input"))
      (node (ref "U1") (pin "19") (pinfunction "DIR_19") (pintype "input"))
      (node (ref "U5") (pin "24") (pinfunction "(PCINT21/TDI)PC5_24") (pintype "output"))
    )
    (net (code "29") (name "/X-STEP") (class "Default")
      (node (ref "T15") (pin "TP") (pinfunction "TP_TP") (pintype "input"))
      (node (ref "T16") (pin "TP") (pinfunction "TP_TP") (pintype "input"))
      (node (ref "U1") (pin "16") (pinfunction "STEP_16") (pintype "input"))
      (node (ref "U5") (pin "16") (pinfunction "(PCINT31/OC2A)PD7_16") (pintype "bidirectional"))
    )
    (net (code "30") (name "/X-STOP") (class "Default")
      (node (ref "C46") (pin "1") (pinfunction "1_1") (pintype "passive"))
      (node (ref "R40") (pin "2") (pinfunction "2_2") (pintype "passive"))
      (node (ref "S_X") (pin "3") (pinfunction "S_3") (pintype "passive"))
      (node (ref "T61") (pin "TP") (pinfunction "TP_TP") (pintype "input"))
      (node (ref "T62") (pin "TP") (pinfunction "TP_TP") (pintype "input"))
      (node (ref "U5") (pin "21") (pinfunction "(PCINT18/TCK)PC2_21") (pintype "output"))
    )
    (net (code "31") (name "/Y-DIR") (class "Default")
      (node (ref "T11") (pin "TP") (pinfunction "TP_TP") (pintype "input"))
      (node (ref "T12") (pin "TP") (pinfunction "TP_TP") (pintype "input"))
      (node (ref "U2") (pin "19") (pinfunction "DIR_19") (pintype "input"))
      (node (ref "U5") (pin "26") (pinfunction "(PCINT23/TOSC2)PC7_26") (pintype "output"))
    )
    (net (code "32") (name "/Y-STEP") (class "Default")
      (node (ref "T10") (pin "TP") (pinfunction "TP_TP") (pintype "input"))
      (node (ref "T9") (pin "TP") (pinfunction "TP_TP") (pintype "input"))
      (node (ref "U2") (pin "16") (pinfunction "STEP_16") (pintype "input"))
      (node (ref "U5") (pin "25") (pinfunction "(PCINT22/TOSC1)PC6_25") (pintype "output"))
    )
    (net (code "33") (name "/Y-STOP") (class "Default")
      (node (ref "C44") (pin "1") (pinfunction "1_1") (pintype "passive"))
      (node (ref "R38") (pin "2") (pinfunction "2_2") (pintype "passive"))
      (node (ref "S_Y") (pin "3") (pinfunction "S_3") (pintype "passive"))
      (node (ref "T57") (pin "TP") (pinfunction "TP_TP") (pintype "input"))
      (node (ref "T58") (pin "TP") (pinfunction "TP_TP") (pintype "input"))
      (node (ref "U5") (pin "22") (pinfunction "(PCINT19/TMS)PC3_22") (pintype "output"))
    )
    (net (code "34") (name "/Z-DIR") (class "Default")
      (node (ref "T3") (pin "TP") (pinfunction "TP_TP") (pintype "input"))
      (node (ref "T4") (pin "TP") (pinfunction "TP_TP") (pintype "input"))
      (node (ref "U4") (pin "19") (pinfunction "DIR_19") (pintype "input"))
      (node (ref "U5") (pin "42") (pinfunction "(PCINT10/INT2/AIN0)PB2_42") (pintype "bidirectional"))
    )
    (net (code "35") (name "/Z-STEP") (class "Default")
      (node (ref "T1") (pin "TP") (pinfunction "TP_TP") (pintype "input"))
      (node (ref "T2") (pin "TP") (pinfunction "TP_TP") (pintype "input"))
      (node (ref "U4") (pin "16") (pinfunction "STEP_16") (pintype "input"))
      (node (ref "U5") (pin "43") (pinfunction "(PCINT11/OC0A/AIN1)PB3_43") (pintype "bidirectional"))
    )
    (net (code "36") (name "/Z-STOP") (class "Default")
      (node (ref "C45") (pin "1") (pinfunction "1_1") (pintype "passive"))
      (node (ref "R39") (pin "2") (pinfunction "2_2") (pintype "passive"))
      (node (ref "S_Z") (pin "3") (pinfunction "S_3") (pintype "passive"))
      (node (ref "T59") (pin "TP") (pinfunction "TP_TP") (pintype "input"))
      (node (ref "T60") (pin "TP") (pinfunction "TP_TP") (pintype "input"))
      (node (ref "U5") (pin "23") (pinfunction "(PCINT20/TDO)PC4_23") (pintype "output"))
    )
    (net (code "37") (name "/~{FAN}") (class "Default")
      (node (ref "J3") (pin "9") (pinfunction "9_9") (pintype "passive"))
      (node (ref "Q3") (pin "1") (pinfunction "G_1") (pintype "passive"))
      (node (ref "R44") (pin "2") (pinfunction "2_2") (pintype "passive"))
      (node (ref "T35") (pin "TP") (pinfunction "TP_TP") (pintype "input"))
      (node (ref "T36") (pin "TP") (pinfunction "TP_TP") (pintype "input"))
      (node (ref "U5") (pin "44") (pinfunction "(PCINT12/OC0B/~{SS})PB4_44") (pintype "bidirectional"))
    )
    (net (code "38") (name "/~{HOTBED}") (class "Default")
      (node (ref "Q1") (pin "1") (pinfunction "G_1") (pintype "passive"))
      (node (ref "R42") (pin "2") (pinfunction "2_2") (pintype "passive"))
      (node (ref "T31") (pin "TP") (pinfunction "TP_TP") (pintype "input"))
      (node (ref "T32") (pin "TP") (pinfunction "TP_TP") (pintype "input"))
      (node (ref "U5") (pin "13") (pinfunction "(PCINT28/OC1B)PD4_13") (pintype "bidirectional"))
    )
    (net (code "39") (name "/~{HOTEND}") (class "Default")
      (node (ref "Q2") (pin "1") (pinfunction "G_1") (pintype "passive"))
      (node (ref "R43") (pin "2") (pinfunction "2_2") (pintype "passive"))
      (node (ref "T29") (pin "TP") (pinfunction "TP_TP") (pintype "input"))
      (node (ref "T30") (pin "TP") (pinfunction "TP_TP") (pintype "input"))
      (node (ref "U5") (pin "14") (pinfunction "(PCINT29/OC1A)PD5_14") (pintype "bidirectional"))
    )
    (net (code "40") (name "/~{RESET}") (class "Default")
      (node (ref "C33") (pin "2") (pinfunction "2_2") (pintype "passive"))
      (node (ref "J3") (pin "7") (pinfunction "7_7") (pintype "passive"))
      (node (ref "R35") (pin "2") (pinfunction "2_2") (pintype "passive"))
      (node (ref "SW1") (pin "3") (pinfunction "3_3") (pintype "passive"))
      (node (ref "SW1") (pin "4") (pinfunction "4_4") (pintype "passive"))
      (node (ref "T33") (pin "TP") (pinfunction "TP_TP") (pintype "input"))
      (node (ref "T34") (pin "TP") (pinfunction "TP_TP") (pintype "input"))
      (node (ref "U5") (pin "4") (pinfunction "RESET_4") (pintype "input"))
    )
    (net (code "41") (name "/~{XY-ENABLE}") (class "Default")
      (node (ref "R15") (pin "2") (pinfunction "2_2") (pintype "passive"))
      (node (ref "R22") (pin "2") (pinfunction "2_2") (pintype "passive"))
      (node (ref "R8") (pin "2") (pinfunction "2_2") (pintype "passive"))
      (node (ref "T19") (pin "TP") (pinfunction "TP_TP") (pintype "input"))
      (node (ref "T20") (pin "TP") (pinfunction "TP_TP") (pintype "input"))
      (node (ref "U1") (pin "2") (pinfunction "~{ENABLE}_2") (pintype "input"))
      (node (ref "U2") (pin "2") (pinfunction "~{ENABLE}_2") (pintype "input"))
      (node (ref "U3") (pin "2") (pinfunction "~{ENABLE}_2") (pintype "input"))
      (node (ref "U5") (pin "15") (pinfunction "(PCINT30/OC2B/ICP)PD6_15") (pintype "bidirectional"))
    )
    (net (code "42") (name "/~{Z-ENABLE}") (class "Default")
      (node (ref "R29") (pin "2") (pinfunction "2_2") (pintype "passive"))
      (node (ref "T17") (pin "TP") (pinfunction "TP_TP") (pintype "input"))
      (node (ref "T18") (pin "TP") (pinfunction "TP_TP") (pintype "input"))
      (node (ref "U4") (pin "2") (pinfunction "~{ENABLE}_2") (pintype "input"))
      (node (ref "U5") (pin "32") (pinfunction "(PCINT5/ADC5)PA5_32") (pintype "bidirectional"))
    )
    (net (code "43") (name "GND") (class "Default")
      (node (ref "B_T") (pin "1") (pinfunction "S_1") (pintype "passive"))
      (node (ref "C11") (pin "1") (pinfunction "1_1") (pintype "passive"))
      (node (ref "C12") (pin "2") (pinfunction "2_2") (pintype "passive"))
      (node (ref "C13") (pin "-") (pinfunction "-_-") (pintype "passive"))
      (node (ref "C15") (pin "2") (pinfunction "2_2") (pintype "passive"))
      (node (ref "C17") (pin "1") (pinfunction "1_1") (pintype "passive"))
      (node (ref "C18") (pin "2") (pinfunction "2_2") (pintype "passive"))
      (node (ref "C19") (pin "-") (pinfunction "-_-") (pintype "passive"))
      (node (ref "C2") (pin "2") (pinfunction "2_2") (pintype "passive"))
      (node (ref "C21") (pin "2") (pinfunction "2_2") (pintype "passive"))
      (node (ref "C23") (pin "1") (pinfunction "1_1") (pintype "passive"))
      (node (ref "C24") (pin "2") (pinfunction "2_2") (pintype "passive"))
      (node (ref "C25") (pin "-") (pinfunction "-_-") (pintype "passive"))
      (node (ref "C26") (pin "2") (pinfunction "2_2") (pintype "passive"))
      (node (ref "C27") (pin "2") (pinfunction "2_2") (pintype "passive"))
      (node (ref "C28") (pin "2") (pinfunction "2_2") (pintype "passive"))
      (node (ref "C30") (pin "2") (pinfunction "2_2") (pintype "passive"))
      (node (ref "C31") (pin "2") (pinfunction "2_2") (pintype "passive"))
      (node (ref "C32") (pin "1") (pinfunction "1_1") (pintype "passive"))
      (node (ref "C34") (pin "2") (pinfunction "2_2") (pintype "passive"))
      (node (ref "C35") (pin "2") (pinfunction "2_2") (pintype "passive"))
      (node (ref "C36") (pin "2") (pinfunction "2_2") (pintype "passive"))
      (node (ref "C37") (pin "2") (pinfunction "2_2") (pintype "passive"))
      (node (ref "C38") (pin "2") (pinfunction "2_2") (pintype "passive"))
      (node (ref "C39") (pin "2") (pinfunction "2_2") (pintype "passive"))
      (node (ref "C40") (pin "2") (pinfunction "2_2") (pintype "passive"))
      (node (ref "C41") (pin "2") (pinfunction "2_2") (pintype "passive"))
      (node (ref "C43") (pin "2") (pinfunction "2_2") (pintype "passive"))
      (node (ref "C44") (pin "2") (pinfunction "2_2") (pintype "passive"))
      (node (ref "C45") (pin "2") (pinfunction "2_2") (pintype "passive"))
      (node (ref "C46") (pin "2") (pinfunction "2_2") (pintype "passive"))
      (node (ref "C47") (pin "2") (pinfunction "2_2") (pintype "passive"))
      (node (ref "C48") (pin "2") (pinfunction "2_2") (pintype "passive"))
      (node (ref "C49") (pin "2") (pinfunction "2_2") (pintype "passive"))
      (node (ref "C5") (pin "1") (pinfunction "1_1") (pintype "passive"))
      (node (ref "C50") (pin "2") (pinfunction "2_2") (pintype "passive"))
      (node (ref "C51") (pin "2") (pinfunction "2_2") (pintype "passive"))
      (node (ref "C52") (pin "-") (pinfunction "-_-") (pintype "passive"))
      (node (ref "C53") (pin "-") (pinfunction "-_-") (pintype "passive"))
      (node (ref "C54") (pin "-") (pinfunction "-_-") (pintype "passive"))
      (node (ref "C55") (pin "-") (pinfunction "-_-") (pintype "passive"))
      (node (ref "C6") (pin "2") (pinfunction "2_2") (pintype "passive"))
      (node (ref "C7") (pin "-") (pinfunction "-_-") (pintype "passive"))
      (node (ref "C9") (pin "2") (pinfunction "2_2") (pintype "passive"))
      (node (ref "E_T") (pin "1") (pinfunction "S_1") (pintype "passive"))
      (node (ref "FAN2") (pin "2") (pinfunction "S_2") (pintype "passive"))
      (node (ref "J3") (pin "8") (pinfunction "8_8") (pintype "passive"))
      (node (ref "J7") (pin "1") (pinfunction "1_1") (pintype "passive"))
      (node (ref "J7") (pin "2") (pinfunction "2_2") (pintype "passive"))
      (node (ref "J9") (pin "4") (pinfunction "4_4") (pintype "passive"))
      (node (ref "J9") (pin "S1") (pinfunction "S1_S1") (pintype "passive"))
      (node (ref "J9") (pin "S2") (pinfunction "S2_S2") (pintype "passive"))
      (node (ref "LCD") (pin "1") (pinfunction "1_1") (pintype "passive"))
      (node (ref "POWER") (pin "2") (pinfunction "2_2") (pintype "passive"))
      (node (ref "Q1") (pin "3") (pinfunction "S_3") (pintype "passive"))
      (node (ref "Q2") (pin "3") (pinfunction "S_3") (pintype "passive"))
      (node (ref "Q3") (pin "3") (pinfunction "S_3") (pintype "passive"))
      (node (ref "Q4") (pin "4") (pinfunction "GND_4") (pintype "bidirectional"))
      (node (ref "R11") (pin "2") (pinfunction "2_2") (pintype "passive"))
      (node (ref "R12") (pin "2") (pinfunction "2_2") (pintype "passive"))
      (node (ref "R13") (pin "2") (pinfunction "2_2") (pintype "passive"))
      (node (ref "R16") (pin "1") (pinfunction "1_1") (pintype "passive"))
      (node (ref "R18") (pin "2") (pinfunction "2_2") (pintype "passive"))
      (node (ref "R19") (pin "2") (pinfunction "2_2") (pintype "passive"))
      (node (ref "R20") (pin "2") (pinfunction "2_2") (pintype "passive"))
      (node (ref "R23") (pin "1") (pinfunction "1_1") (pintype "passive"))
      (node (ref "R25") (pin "2") (pinfunction "2_2") (pintype "passive"))
      (node (ref "R26") (pin "2") (pinfunction "2_2") (pintype "passive"))
      (node (ref "R27") (pin "2") (pinfunction "2_2") (pintype "passive"))
      (node (ref "R30") (pin "1") (pinfunction "A_1") (pintype "passive"))
      (node (ref "R32") (pin "2") (pinfunction "2_2") (pintype "passive"))
      (node (ref "R33") (pin "2") (pinfunction "2_2") (pintype "passive"))
      (node (ref "R34") (pin "2") (pinfunction "2_2") (pintype "passive"))
      (node (ref "R42") (pin "1") (pinfunction "1_1") (pintype "passive"))
      (node (ref "R43") (pin "1") (pinfunction "1_1") (pintype "passive"))
      (node (ref "R44") (pin "1") (pinfunction "1_1") (pintype "passive"))
      (node (ref "R45") (pin "1") (pinfunction "1_1") (pintype "passive"))
      (node (ref "R9") (pin "1") (pinfunction "1_1") (pintype "passive"))
      (node (ref "SD") (pin "6") (pinfunction "VSS_6") (pintype "power_in"))
      (node (ref "SD") (pin "8") (pinfunction "DAT1_8") (pintype "bidirectional"))
      (node (ref "SD") (pin "9") (pinfunction "CARD_DETECT_9") (pintype "passive"))
      (node (ref "SD") (pin "GND") (pinfunction "GND_GND") (pintype "power_in"))
      (node (ref "SD") (pin "GND2") (pinfunction "GND1_GND2") (pintype "power_in"))
      (node (ref "SD") (pin "GND3") (pinfunction "GND2_GND3") (pintype "power_in"))
      (node (ref "SD") (pin "GND4") (pinfunction "GND3_GND4") (pintype "power_in"))
      (node (ref "SW1") (pin "1") (pinfunction "1_1") (pintype "passive"))
      (node (ref "SW1") (pin "2") (pinfunction "2_2") (pintype "passive"))
      (node (ref "S_X") (pin "1") (pinfunction "S_1") (pintype "passive"))
      (node (ref "S_Y") (pin "1") (pinfunction "S_1") (pintype "passive"))
      (node (ref "S_Z") (pin "1") (pinfunction "S_1") (pintype "passive"))
      (node (ref "U1") (pin "18") (pinfunction "GND_2_18") (pintype "passive"))
      (node (ref "U1") (pin "29") (pinfunction "PAD_29") (pintype "passive"))
      (node (ref "U1") (pin "3") (pinfunction "GND_3") (pintype "passive"))
      (node (ref "U10") (pin "1") (pinfunction "GND_1") (pintype "input"))
      (node (ref "U2") (pin "18") (pinfunction "GND_2_18") (pintype "passive"))
      (node (ref "U2") (pin "29") (pinfunction "PAD_29") (pintype "passive"))
      (node (ref "U2") (pin "3") (pinfunction "GND_3") (pintype "passive"))
      (node (ref "U3") (pin "18") (pinfunction "GND_2_18") (pintype "passive"))
      (node (ref "U3") (pin "29") (pinfunction "PAD_29") (pintype "passive"))
      (node (ref "U3") (pin "3") (pinfunction "GND_3") (pintype "passive"))
      (node (ref "U4") (pin "18") (pinfunction "GND_2_18") (pintype "passive"))
      (node (ref "U4") (pin "29") (pinfunction "PAD_29") (pintype "passive"))
      (node (ref "U4") (pin "3") (pinfunction "GND_3") (pintype "passive"))
      (node (ref "U5") (pin "18") (pinfunction "GND_18") (pintype "power_in"))
      (node (ref "U5") (pin "28") (pinfunction "GND_28") (pintype "power_in"))
      (node (ref "U5") (pin "39") (pinfunction "GND_39") (pintype "power_in"))
      (node (ref "U5") (pin "6") (pinfunction "GND_6") (pintype "power_in"))
      (node (ref "U6") (pin "1") (pinfunction "GND_1") (pintype "bidirectional"))
      (node (ref "U8") (pin "8") (pinfunction "VSS_8") (pintype "power_in"))
    )
    (net (code "44") (name "Net-(D1-PadC)") (class "Default")
      (node (ref "D1") (pin "C") (pinfunction "C_C") (pintype "passive"))
      (node (ref "R45") (pin "2") (pinfunction "2_2") (pintype "passive"))
    )
    (net (code "45") (name "Net-(D4-PadC)") (class "Default")
      (node (ref "D4") (pin "C") (pinfunction "C_C") (pintype "passive"))
      (node (ref "R49") (pin "2") (pinfunction "2_2") (pintype "passive"))
    )
    (net (code "46") (name "Net-(D5-PadC)") (class "Default")
      (node (ref "D5") (pin "C") (pinfunction "C_C") (pintype "passive"))
      (node (ref "R50") (pin "2") (pinfunction "2_2") (pintype "passive"))
    )
    (net (code "47") (name "Net-(D6-PadC)") (class "Default")
      (node (ref "D6") (pin "C") (pinfunction "C_C") (pintype "passive"))
      (node (ref "R51") (pin "2") (pinfunction "2_2") (pintype "passive"))
    )
    (net (code "48") (name "Net-(E-MOTORA-S)") (class "Default")
      (node (ref "E-MOTOR") (pin "1") (pinfunction "S_1") (pintype "passive"))
      (node (ref "U3") (pin "1") (pinfunction "OUT2B_1") (pintype "output"))
    )
    (net (code "49") (name "Net-(E-MOTORB-S)") (class "Default")
      (node (ref "E-MOTOR") (pin "2") (pinfunction "S_2") (pintype "passive"))
      (node (ref "U3") (pin "26") (pinfunction "OUT2A_26") (pintype "output"))
    )
    (net (code "50") (name "Net-(E-MOTORC-S)") (class "Default")
      (node (ref "E-MOTOR") (pin "3") (pinfunction "S_3") (pintype "passive"))
      (node (ref "U3") (pin "24") (pinfunction "OUT1A_24") (pintype "output"))
    )
    (net (code "51") (name "Net-(E-MOTORD-S)") (class "Default")
      (node (ref "E-MOTOR") (pin "4") (pinfunction "S_4") (pintype "passive"))
      (node (ref "U3") (pin "21") (pinfunction "OUT1B_21") (pintype "output"))
    )
    (net (code "52") (name "Net-(FAN1B-S)") (class "Default")
      (node (ref "FAN1") (pin "2") (pinfunction "S_2") (pintype "passive"))
      (node (ref "Q3") (pin "4") (pinfunction "D_4") (pintype "passive"))
      (node (ref "R51") (pin "1") (pinfunction "1_1") (pintype "passive"))
    )
    (net (code "53") (name "Net-(Q1-D)") (class "Default")
      (node (ref "BED") (pin "2") (pinfunction "2_2") (pintype "passive"))
      (node (ref "Q1") (pin "4") (pinfunction "D_4") (pintype "passive"))
      (node (ref "R49") (pin "1") (pinfunction "1_1") (pintype "passive"))
    )
    (net (code "54") (name "Net-(Q2-D)") (class "Default")
      (node (ref "END") (pin "2") (pinfunction "2_2") (pintype "passive"))
      (node (ref "Q2") (pin "4") (pinfunction "D_4") (pintype "passive"))
      (node (ref "R50") (pin "1") (pinfunction "1_1") (pintype "passive"))
    )
    (net (code "55") (name "Net-(R30-E)") (class "Default")
      (node (ref "R30") (pin "3") (pinfunction "E_3") (pintype "passive"))
      (node (ref "R31") (pin "1") (pinfunction "1_1") (pintype "passive"))
    )
    (net (code "56") (name "Net-(R30-S)") (class "Default")
      (node (ref "R30") (pin "2") (pinfunction "S_2") (pintype "passive"))
      (node (ref "U4") (pin "17") (pinfunction "REF_17") (pintype "input"))
    )
    (net (code "57") (name "Net-(SD-CS)") (class "Default")
      (node (ref "SD") (pin "2") (pinfunction "CS_2") (pintype "input"))
      (node (ref "U8") (pin "6") (pinfunction "O_6") (pintype "output"))
    )
    (net (code "58") (name "Net-(SD-DATA_IN)") (class "Default")
      (node (ref "SD") (pin "3") (pinfunction "DATA_IN_3") (pintype "input"))
      (node (ref "U8") (pin "2") (pinfunction "O_2") (pintype "output"))
    )
    (net (code "59") (name "Net-(SD-SCLK)") (class "Default")
      (node (ref "SD") (pin "5") (pinfunction "SCLK_5") (pintype "input"))
      (node (ref "U8") (pin "4") (pinfunction "O_4") (pintype "output"))
    )
    (net (code "60") (name "Net-(U1-CP1)") (class "Default")
      (node (ref "C1") (pin "2") (pinfunction "2_2") (pintype "passive"))
      (node (ref "U1") (pin "4") (pinfunction "CP1_4") (pintype "passive"))
    )
    (net (code "61") (name "Net-(U1-CP2)") (class "Default")
      (node (ref "C1") (pin "1") (pinfunction "1_1") (pintype "passive"))
      (node (ref "U1") (pin "5") (pinfunction "CP2_5") (pintype "passive"))
    )
    (net (code "62") (name "Net-(U1-OUT1A)") (class "Default")
      (node (ref "U1") (pin "24") (pinfunction "OUT1A_24") (pintype "output"))
      (node (ref "X-MOTOR") (pin "3") (pinfunction "S_3") (pintype "passive"))
    )
    (net (code "63") (name "Net-(U1-OUT1B)") (class "Default")
      (node (ref "U1") (pin "21") (pinfunction "OUT1B_21") (pintype "output"))
      (node (ref "X-MOTOR") (pin "4") (pinfunction "S_4") (pintype "passive"))
    )
    (net (code "64") (name "Net-(U1-OUT2A)") (class "Default")
      (node (ref "U1") (pin "26") (pinfunction "OUT2A_26") (pintype "output"))
      (node (ref "X-MOTOR") (pin "2") (pinfunction "S_2") (pintype "passive"))
    )
    (net (code "65") (name "Net-(U1-OUT2B)") (class "Default")
      (node (ref "U1") (pin "1") (pinfunction "OUT2B_1") (pintype "output"))
      (node (ref "X-MOTOR") (pin "1") (pinfunction "S_1") (pintype "passive"))
    )
    (net (code "66") (name "Net-(U1-REF)") (class "Default")
      (node (ref "R10") (pin "1") (pinfunction "1_1") (pintype "passive"))
      (node (ref "R9") (pin "2") (pinfunction "2_2") (pintype "passive"))
      (node (ref "U1") (pin "17") (pinfunction "REF_17") (pintype "input"))
    )
    (net (code "67") (name "Net-(U1-ROSC)") (class "Default")
      (node (ref "R13") (pin "1") (pinfunction "1_1") (pintype "passive"))
      (node (ref "U1") (pin "13") (pinfunction "ROSC_13") (pintype "input"))
    )
    (net (code "68") (name "Net-(U1-SENSE1)") (class "Default")
      (node (ref "R11") (pin "1") (pinfunction "1_1") (pintype "passive"))
      (node (ref "U1") (pin "23") (pinfunction "SENSE1_23") (pintype "input"))
    )
    (net (code "69") (name "Net-(U1-SENSE2)") (class "Default")
      (node (ref "R12") (pin "1") (pinfunction "1_1") (pintype "passive"))
      (node (ref "U1") (pin "27") (pinfunction "SENSE2_27") (pintype "input"))
    )
    (net (code "70") (name "Net-(U1-VCP)") (class "Default")
      (node (ref "C4") (pin "2") (pinfunction "2_2") (pintype "passive"))
      (node (ref "U1") (pin "6") (pinfunction "VCP_6") (pintype "passive"))
    )
    (net (code "71") (name "Net-(U1-VREG)") (class "Default")
      (node (ref "C5") (pin "2") (pinfunction "2_2") (pintype "passive"))
      (node (ref "U1") (pin "8") (pinfunction "VREG_8") (pintype "passive"))
    )
    (net (code "72") (name "Net-(U1-~{RESET})") (class "Default")
      (node (ref "R7") (pin "2") (pinfunction "2_2") (pintype "passive"))
      (node (ref "U1") (pin "12") (pinfunction "~{RESET}_12") (pintype "input"))
      (node (ref "U1") (pin "14") (pinfunction "~{SLEEP}_14") (pintype "input"))
    )
    (net (code "73") (name "Net-(U2-CP1)") (class "Default")
      (node (ref "C8") (pin "2") (pinfunction "2_2") (pintype "passive"))
      (node (ref "U2") (pin "4") (pinfunction "CP1_4") (pintype "passive"))
    )
    (net (code "74") (name "Net-(U2-CP2)") (class "Default")
      (node (ref "C8") (pin "1") (pinfunction "1_1") (pintype "passive"))
      (node (ref "U2") (pin "5") (pinfunction "CP2_5") (pintype "passive"))
    )
    (net (code "75") (name "Net-(U2-OUT1A)") (class "Default")
      (node (ref "U2") (pin "24") (pinfunction "OUT1A_24") (pintype "output"))
      (node (ref "Y-MOTOR") (pin "3") (pinfunction "S_3") (pintype "passive"))
    )
    (net (code "76") (name "Net-(U2-OUT1B)") (class "Default")
      (node (ref "U2") (pin "21") (pinfunction "OUT1B_21") (pintype "output"))
      (node (ref "Y-MOTOR") (pin "4") (pinfunction "S_4") (pintype "passive"))
    )
    (net (code "77") (name "Net-(U2-OUT2A)") (class "Default")
      (node (ref "U2") (pin "26") (pinfunction "OUT2A_26") (pintype "output"))
      (node (ref "Y-MOTOR") (pin "2") (pinfunction "S_2") (pintype "passive"))
    )
    (net (code "78") (name "Net-(U2-OUT2B)") (class "Default")
      (node (ref "U2") (pin "1") (pinfunction "OUT2B_1") (pintype "output"))
      (node (ref "Y-MOTOR") (pin "1") (pinfunction "S_1") (pintype "passive"))
    )
    (net (code "79") (name "Net-(U2-REF)") (class "Default")
      (node (ref "R16") (pin "2") (pinfunction "2_2") (pintype "passive"))
      (node (ref "R17") (pin "1") (pinfunction "1_1") (pintype "passive"))
      (node (ref "U2") (pin "17") (pinfunction "REF_17") (pintype "input"))
    )
    (net (code "80") (name "Net-(U2-ROSC)") (class "Default")
      (node (ref "R20") (pin "1") (pinfunction "1_1") (pintype "passive"))
      (node (ref "U2") (pin "13") (pinfunction "ROSC_13") (pintype "input"))
    )
    (net (code "81") (name "Net-(U2-SENSE1)") (class "Default")
      (node (ref "R18") (pin "1") (pinfunction "1_1") (pintype "passive"))
      (node (ref "U2") (pin "23") (pinfunction "SENSE1_23") (pintype "input"))
    )
    (net (code "82") (name "Net-(U2-SENSE2)") (class "Default")
      (node (ref "R19") (pin "1") (pinfunction "1_1") (pintype "passive"))
      (node (ref "U2") (pin "27") (pinfunction "SENSE2_27") (pintype "input"))
    )
    (net (code "83") (name "Net-(U2-VCP)") (class "Default")
      (node (ref "C10") (pin "2") (pinfunction "2_2") (pintype "passive"))
      (node (ref "U2") (pin "6") (pinfunction "VCP_6") (pintype "passive"))
    )
    (net (code "84") (name "Net-(U2-VREG)") (class "Default")
      (node (ref "C11") (pin "2") (pinfunction "2_2") (pintype "passive"))
      (node (ref "U2") (pin "8") (pinfunction "VREG_8") (pintype "passive"))
    )
    (net (code "85") (name "Net-(U2-~{RESET})") (class "Default")
      (node (ref "R14") (pin "2") (pinfunction "2_2") (pintype "passive"))
      (node (ref "U2") (pin "12") (pinfunction "~{RESET}_12") (pintype "input"))
      (node (ref "U2") (pin "14") (pinfunction "~{SLEEP}_14") (pintype "input"))
    )
    (net (code "86") (name "Net-(U3-CP1)") (class "Default")
      (node (ref "C14") (pin "2") (pinfunction "2_2") (pintype "passive"))
      (node (ref "U3") (pin "4") (pinfunction "CP1_4") (pintype "passive"))
    )
    (net (code "87") (name "Net-(U3-CP2)") (class "Default")
      (node (ref "C14") (pin "1") (pinfunction "1_1") (pintype "passive"))
      (node (ref "U3") (pin "5") (pinfunction "CP2_5") (pintype "passive"))
    )
    (net (code "88") (name "Net-(U3-REF)") (class "Default")
      (node (ref "R23") (pin "2") (pinfunction "2_2") (pintype "passive"))
      (node (ref "R24") (pin "1") (pinfunction "1_1") (pintype "passive"))
      (node (ref "U3") (pin "17") (pinfunction "REF_17") (pintype "input"))
    )
    (net (code "89") (name "Net-(U3-ROSC)") (class "Default")
      (node (ref "R27") (pin "1") (pinfunction "1_1") (pintype "passive"))
      (node (ref "U3") (pin "13") (pinfunction "ROSC_13") (pintype "input"))
    )
    (net (code "90") (name "Net-(U3-SENSE1)") (class "Default")
      (node (ref "R25") (pin "1") (pinfunction "1_1") (pintype "passive"))
      (node (ref "U3") (pin "23") (pinfunction "SENSE1_23") (pintype "input"))
    )
    (net (code "91") (name "Net-(U3-SENSE2)") (class "Default")
      (node (ref "R26") (pin "1") (pinfunction "1_1") (pintype "passive"))
      (node (ref "U3") (pin "27") (pinfunction "SENSE2_27") (pintype "input"))
    )
    (net (code "92") (name "Net-(U3-VCP)") (class "Default")
      (node (ref "C16") (pin "2") (pinfunction "2_2") (pintype "passive"))
      (node (ref "U3") (pin "6") (pinfunction "VCP_6") (pintype "passive"))
    )
    (net (code "93") (name "Net-(U3-VREG)") (class "Default")
      (node (ref "C17") (pin "2") (pinfunction "2_2") (pintype "passive"))
      (node (ref "U3") (pin "8") (pinfunction "VREG_8") (pintype "passive"))
    )
    (net (code "94") (name "Net-(U3-~{RESET})") (class "Default")
      (node (ref "R21") (pin "2") (pinfunction "2_2") (pintype "passive"))
      (node (ref "U3") (pin "12") (pinfunction "~{RESET}_12") (pintype "input"))
      (node (ref "U3") (pin "14") (pinfunction "~{SLEEP}_14") (pintype "input"))
    )
    (net (code "95") (name "Net-(U4-CP1)") (class "Default")
      (node (ref "C20") (pin "2") (pinfunction "2_2") (pintype "passive"))
      (node (ref "U4") (pin "4") (pinfunction "CP1_4") (pintype "passive"))
    )
    (net (code "96") (name "Net-(U4-CP2)") (class "Default")
      (node (ref "C20") (pin "1") (pinfunction "1_1") (pintype "passive"))
      (node (ref "U4") (pin "5") (pinfunction "CP2_5") (pintype "passive"))
    )
    (net (code "97") (name "Net-(U4-OUT1A)") (class "Default")
      (node (ref "U4") (pin "24") (pinfunction "OUT1A_24") (pintype "output"))
      (node (ref "Z-MOTOR1") (pin "3") (pinfunction "S_3") (pintype "passive"))
      (node (ref "Z-MOTOR2") (pin "3") (pinfunction "S_3") (pintype "passive"))
    )
    (net (code "98") (name "Net-(U4-OUT1B)") (class "Default")
      (node (ref "U4") (pin "21") (pinfunction "OUT1B_21") (pintype "output"))
      (node (ref "Z-MOTOR1") (pin "4") (pinfunction "S_4") (pintype "passive"))
      (node (ref "Z-MOTOR2") (pin "4") (pinfunction "S_4") (pintype "passive"))
    )
    (net (code "99") (name "Net-(U4-OUT2A)") (class "Default")
      (node (ref "U4") (pin "26") (pinfunction "OUT2A_26") (pintype "output"))
      (node (ref "Z-MOTOR1") (pin "2") (pinfunction "S_2") (pintype "passive"))
      (node (ref "Z-MOTOR2") (pin "2") (pinfunction "S_2") (pintype "passive"))
    )
    (net (code "100") (name "Net-(U4-OUT2B)") (class "Default")
      (node (ref "U4") (pin "1") (pinfunction "OUT2B_1") (pintype "output"))
      (node (ref "Z-MOTOR1") (pin "1") (pinfunction "S_1") (pintype "passive"))
      (node (ref "Z-MOTOR2") (pin "1") (pinfunction "S_1") (pintype "passive"))
    )
    (net (code "101") (name "Net-(U4-ROSC)") (class "Default")
      (node (ref "R34") (pin "1") (pinfunction "1_1") (pintype "passive"))
      (node (ref "U4") (pin "13") (pinfunction "ROSC_13") (pintype "input"))
    )
    (net (code "102") (name "Net-(U4-SENSE1)") (class "Default")
      (node (ref "R32") (pin "1") (pinfunction "1_1") (pintype "passive"))
      (node (ref "U4") (pin "23") (pinfunction "SENSE1_23") (pintype "input"))
    )
    (net (code "103") (name "Net-(U4-SENSE2)") (class "Default")
      (node (ref "R33") (pin "1") (pinfunction "1_1") (pintype "passive"))
      (node (ref "U4") (pin "27") (pinfunction "SENSE2_27") (pintype "input"))
    )
    (net (code "104") (name "Net-(U4-VCP)") (class "Default")
      (node (ref "C22") (pin "2") (pinfunction "2_2") (pintype "passive"))
      (node (ref "U4") (pin "6") (pinfunction "VCP_6") (pintype "passive"))
    )
    (net (code "105") (name "Net-(U4-VREG)") (class "Default")
      (node (ref "C23") (pin "2") (pinfunction "2_2") (pintype "passive"))
      (node (ref "U4") (pin "8") (pinfunction "VREG_8") (pintype "passive"))
    )
    (net (code "106") (name "Net-(U4-~{RESET})") (class "Default")
      (node (ref "R28") (pin "2") (pinfunction "2_2") (pintype "passive"))
      (node (ref "U4") (pin "12") (pinfunction "~{RESET}_12") (pintype "input"))
      (node (ref "U4") (pin "14") (pinfunction "~{SLEEP}_14") (pintype "input"))
    )
    (net (code "107") (name "Net-(U5-XTAL1)") (class "Default")
      (node (ref "C30") (pin "1") (pinfunction "1_1") (pintype "passive"))
      (node (ref "U5") (pin "8") (pinfunction "XTAL1_8") (pintype "bidirectional"))
      (node (ref "Y1") (pin "2") (pinfunction "2_2") (pintype "passive"))
    )
    (net (code "108") (name "Net-(U5-XTAL2)") (class "Default")
      (node (ref "C31") (pin "1") (pinfunction "1_1") (pintype "passive"))
      (node (ref "U5") (pin "7") (pinfunction "XTAL2_7") (pintype "bidirectional"))
      (node (ref "Y1") (pin "1") (pinfunction "1_1") (pintype "passive"))
    )
    (net (code "109") (name "Net-(U6-DTR)") (class "Default")
      (node (ref "C33") (pin "1") (pinfunction "1_1") (pintype "passive"))
      (node (ref "U6") (pin "13") (pinfunction "DTR_13") (pintype "bidirectional"))
    )
    (net (code "110") (name "Net-(U6-V3)") (class "Default")
      (node (ref "C32") (pin "2") (pinfunction "2_2") (pintype "passive"))
      (node (ref "U6") (pin "4") (pinfunction "V3_4") (pintype "bidirectional"))
    )
    (net (code "111") (name "Net-(U6-XI)") (class "Default")
      (node (ref "C34") (pin "1") (pinfunction "1_1") (pintype "passive"))
      (node (ref "U6") (pin "7") (pinfunction "XI_7") (pintype "bidirectional"))
      (node (ref "Y2") (pin "1") (pinfunction "1_1") (pintype "passive"))
    )
    (net (code "112") (name "Net-(U6-XO)") (class "Default")
      (node (ref "C35") (pin "1") (pinfunction "1_1") (pintype "passive"))
      (node (ref "U6") (pin "8") (pinfunction "XO_8") (pintype "bidirectional"))
      (node (ref "Y2") (pin "2") (pinfunction "2_2") (pintype "passive"))
    )
    (net (code "113") (name "unconnected-(B_TB-S-Pad2)") (class "Default")
      (node (ref "B_T") (pin "2") (pinfunction "S_2") (pintype "passive"))
    )
    (net (code "114") (name "unconnected-(E_TB-S-Pad2)") (class "Default")
      (node (ref "E_T") (pin "2") (pinfunction "S_2") (pintype "passive"))
    )
    (net (code "115") (name "unconnected-(J9-Pad1)") (class "Default")
      (node (ref "J9") (pin "1") (pinfunction "1_1") (pintype "passive"))
    )
    (net (code "116") (name "unconnected-(SD-DAT2-Pad1)") (class "Default")
      (node (ref "SD") (pin "1") (pinfunction "DAT2_1") (pintype "bidirectional"))
    )
    (net (code "117") (name "unconnected-(U1-NC-Pad7)") (class "Default")
      (node (ref "U1") (pin "7") (pinfunction "NC_7") (pintype "no_connect"))
    )
    (net (code "118") (name "unconnected-(U1-NC_2-Pad20)") (class "Default")
      (node (ref "U1") (pin "20") (pinfunction "NC_2_20") (pintype "no_connect"))
    )
    (net (code "119") (name "unconnected-(U1-NC_3-Pad25)") (class "Default")
      (node (ref "U1") (pin "25") (pinfunction "NC_3_25") (pintype "no_connect"))
    )
    (net (code "120") (name "unconnected-(U2-NC-Pad7)") (class "Default")
      (node (ref "U2") (pin "7") (pinfunction "NC_7") (pintype "no_connect"))
    )
    (net (code "121") (name "unconnected-(U2-NC_2-Pad20)") (class "Default")
      (node (ref "U2") (pin "20") (pinfunction "NC_2_20") (pintype "no_connect"))
    )
    (net (code "122") (name "unconnected-(U2-NC_3-Pad25)") (class "Default")
      (node (ref "U2") (pin "25") (pinfunction "NC_3_25") (pintype "no_connect"))
    )
    (net (code "123") (name "unconnected-(U3-NC-Pad7)") (class "Default")
      (node (ref "U3") (pin "7") (pinfunction "NC_7") (pintype "no_connect"))
    )
    (net (code "124") (name "unconnected-(U3-NC_2-Pad20)") (class "Default")
      (node (ref "U3") (pin "20") (pinfunction "NC_2_20") (pintype "no_connect"))
    )
    (net (code "125") (name "unconnected-(U3-NC_3-Pad25)") (class "Default")
      (node (ref "U3") (pin "25") (pinfunction "NC_3_25") (pintype "no_connect"))
    )
    (net (code "126") (name "unconnected-(U4-NC-Pad7)") (class "Default")
      (node (ref "U4") (pin "7") (pinfunction "NC_7") (pintype "no_connect"))
    )
    (net (code "127") (name "unconnected-(U4-NC_2-Pad20)") (class "Default")
      (node (ref "U4") (pin "20") (pinfunction "NC_2_20") (pintype "no_connect"))
    )
    (net (code "128") (name "unconnected-(U4-NC_3-Pad25)") (class "Default")
      (node (ref "U4") (pin "25") (pinfunction "NC_3_25") (pintype "no_connect"))
    )
    (net (code "129") (name "unconnected-(U6-CTS-Pad9)") (class "Default")
      (node (ref "U6") (pin "9") (pinfunction "CTS_9") (pintype "bidirectional"))
    )
    (net (code "130") (name "unconnected-(U6-DCD-Pad12)") (class "Default")
      (node (ref "U6") (pin "12") (pinfunction "DCD_12") (pintype "bidirectional"))
    )
    (net (code "131") (name "unconnected-(U6-DSR-Pad10)") (class "Default")
      (node (ref "U6") (pin "10") (pinfunction "DSR_10") (pintype "bidirectional"))
    )
    (net (code "132") (name "unconnected-(U6-RI-Pad11)") (class "Default")
      (node (ref "U6") (pin "11") (pinfunction "RI_11") (pintype "bidirectional"))
    )
    (net (code "133") (name "unconnected-(U6-RS232-Pad15)") (class "Default")
      (node (ref "U6") (pin "15") (pinfunction "RS232_15") (pintype "bidirectional"))
    )
    (net (code "134") (name "unconnected-(U6-RTS-Pad14)") (class "Default")
      (node (ref "U6") (pin "14") (pinfunction "RTS_14") (pintype "bidirectional"))
    )
  )
)
